# EEZ_DIB_DCM220_r2B5.net
KiCad netlist of a schematic drawn in EAGLE
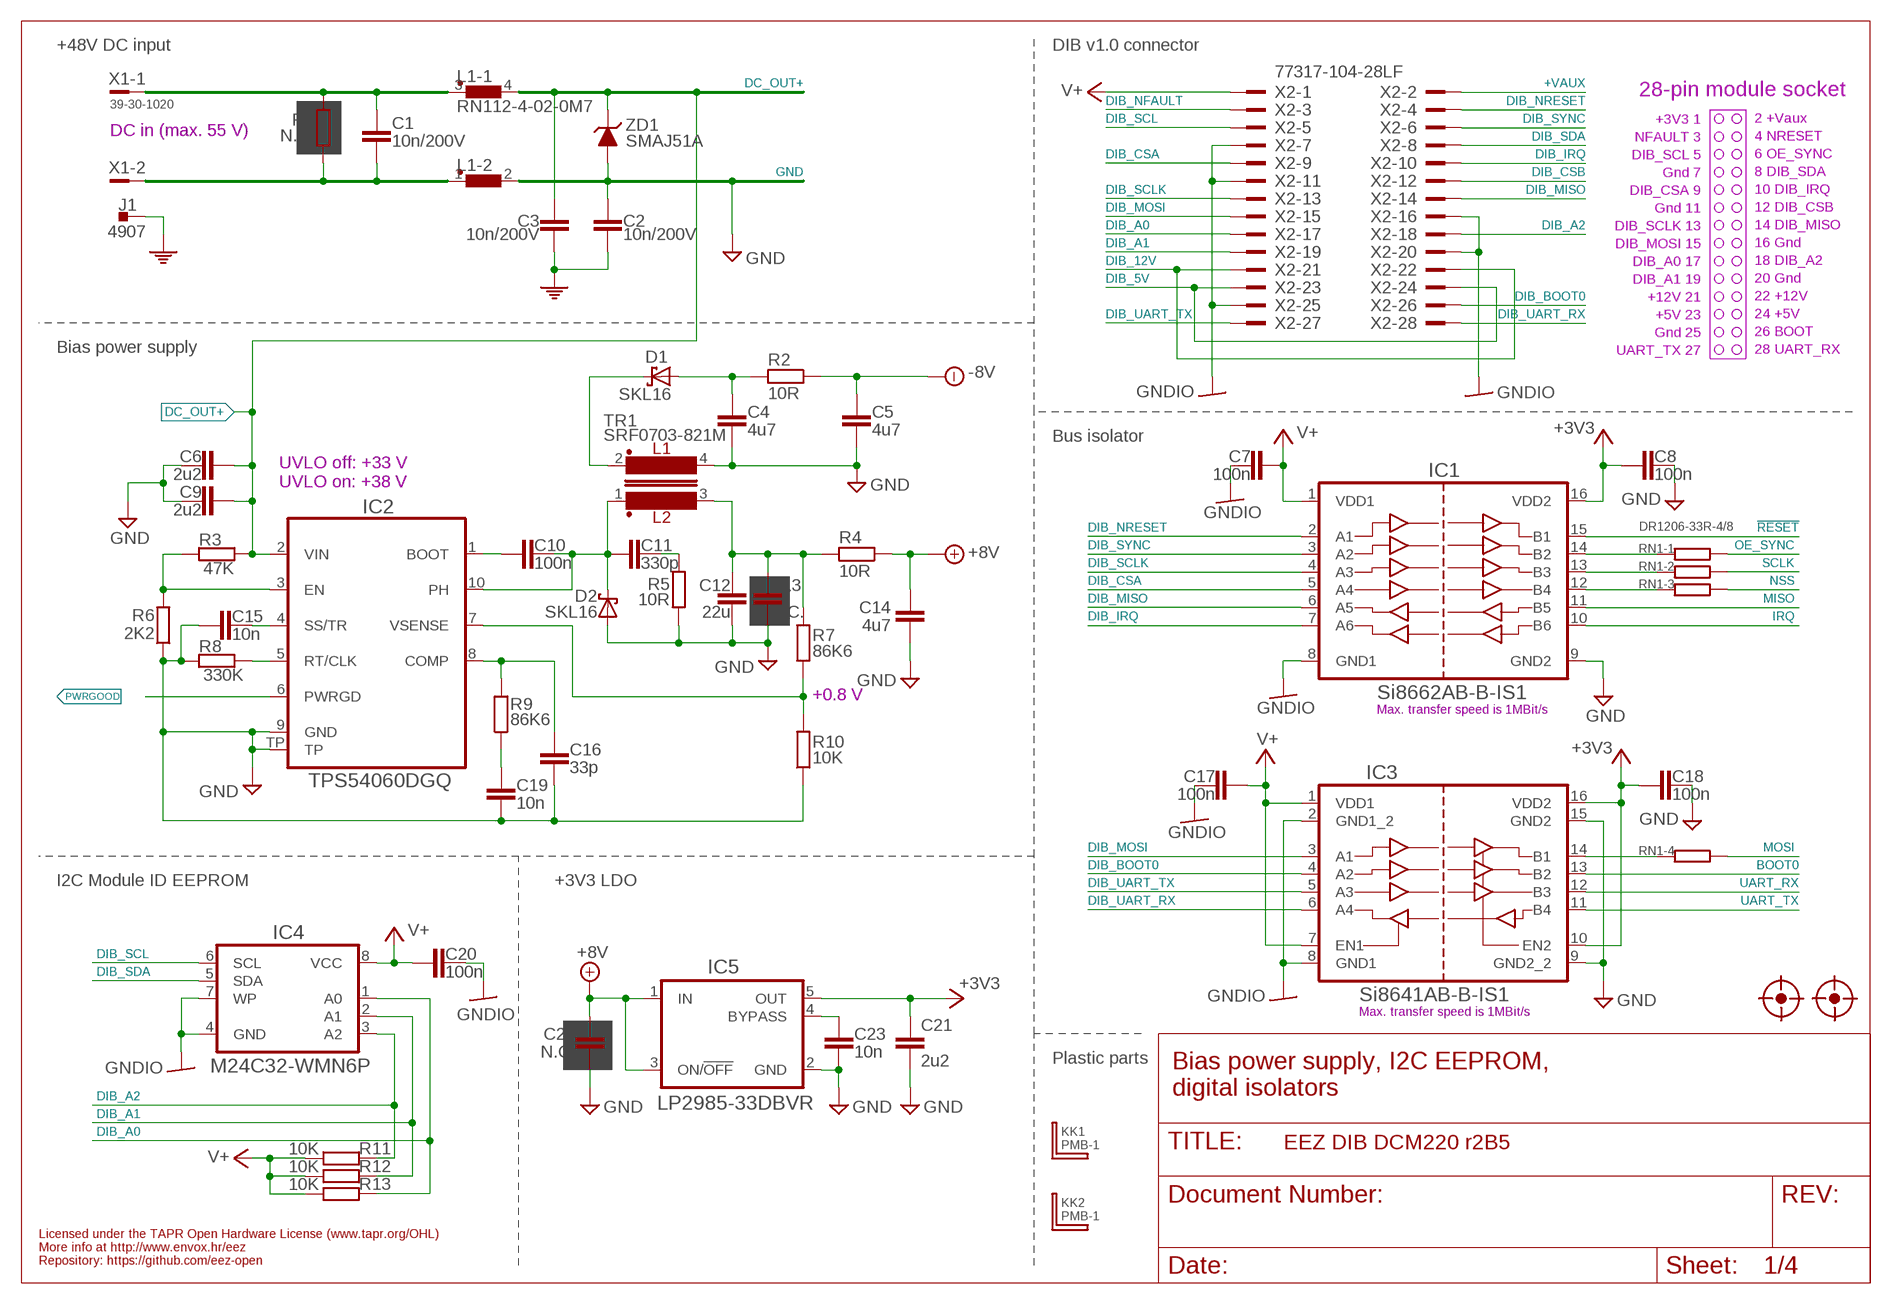
[diagram p0: schematic, sheet 1]
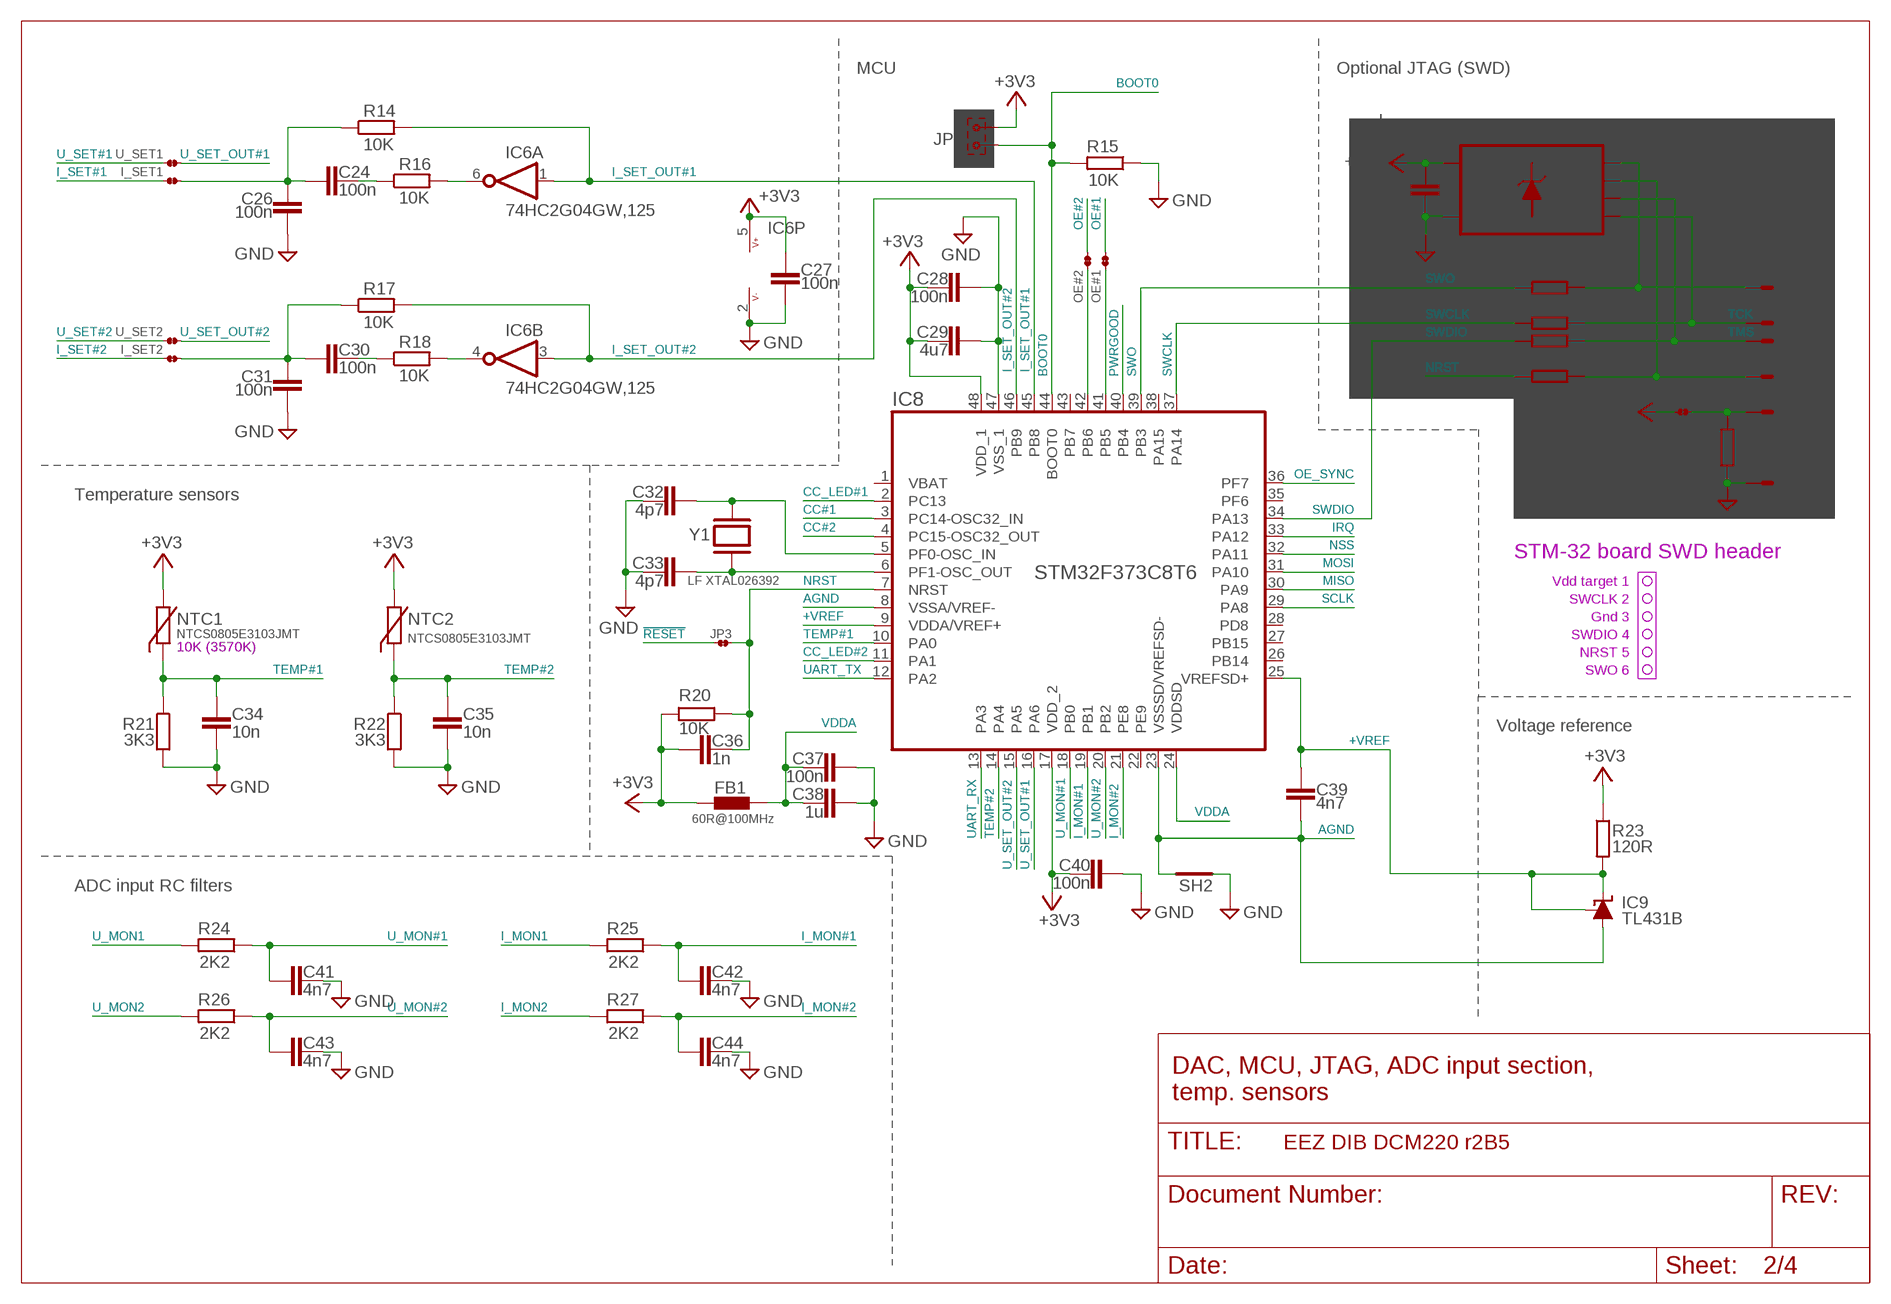
[diagram p1: schematic, sheet 2]
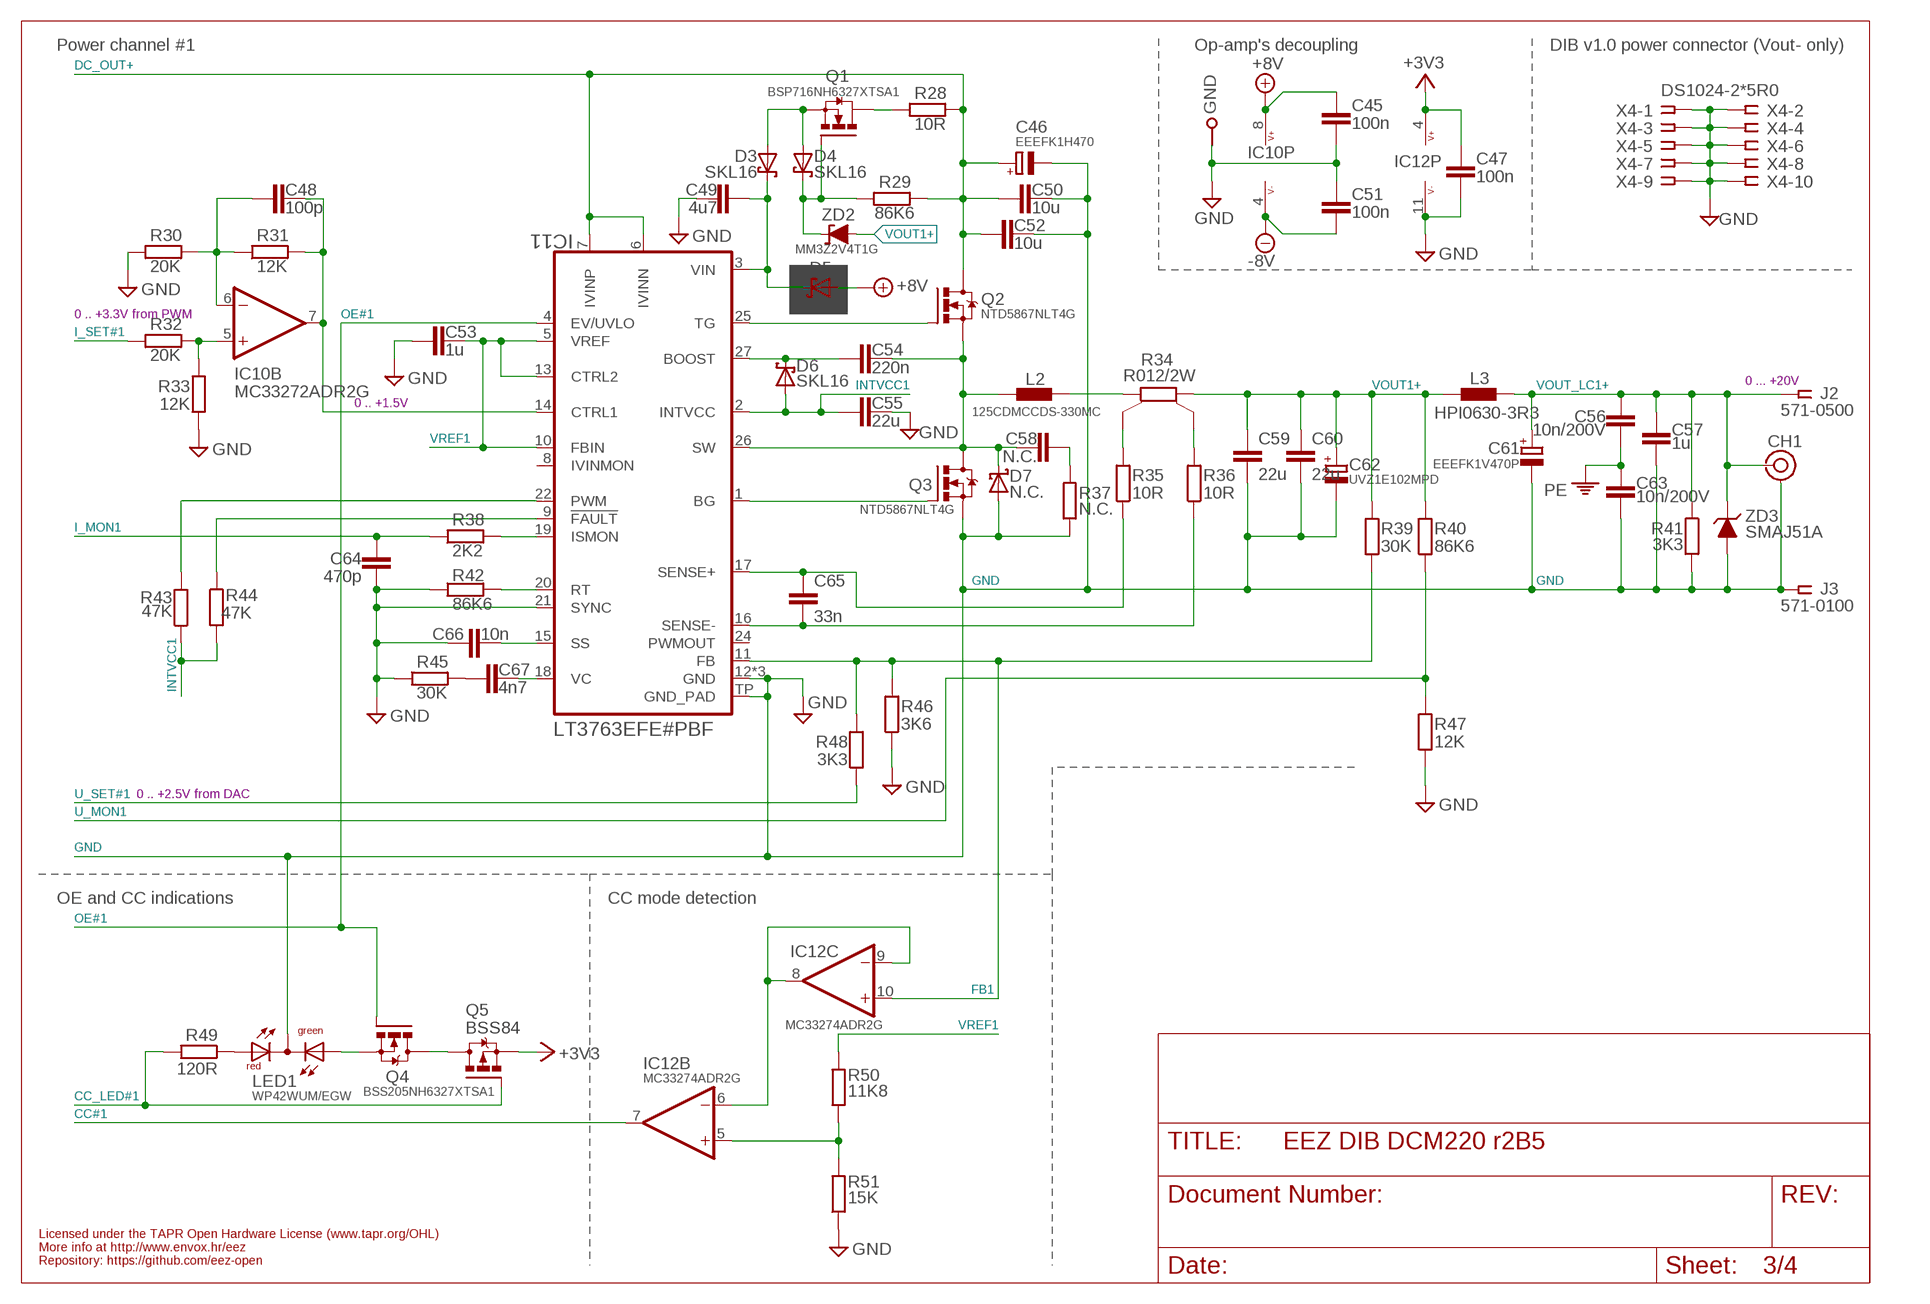
[diagram p2: schematic, sheet 3]
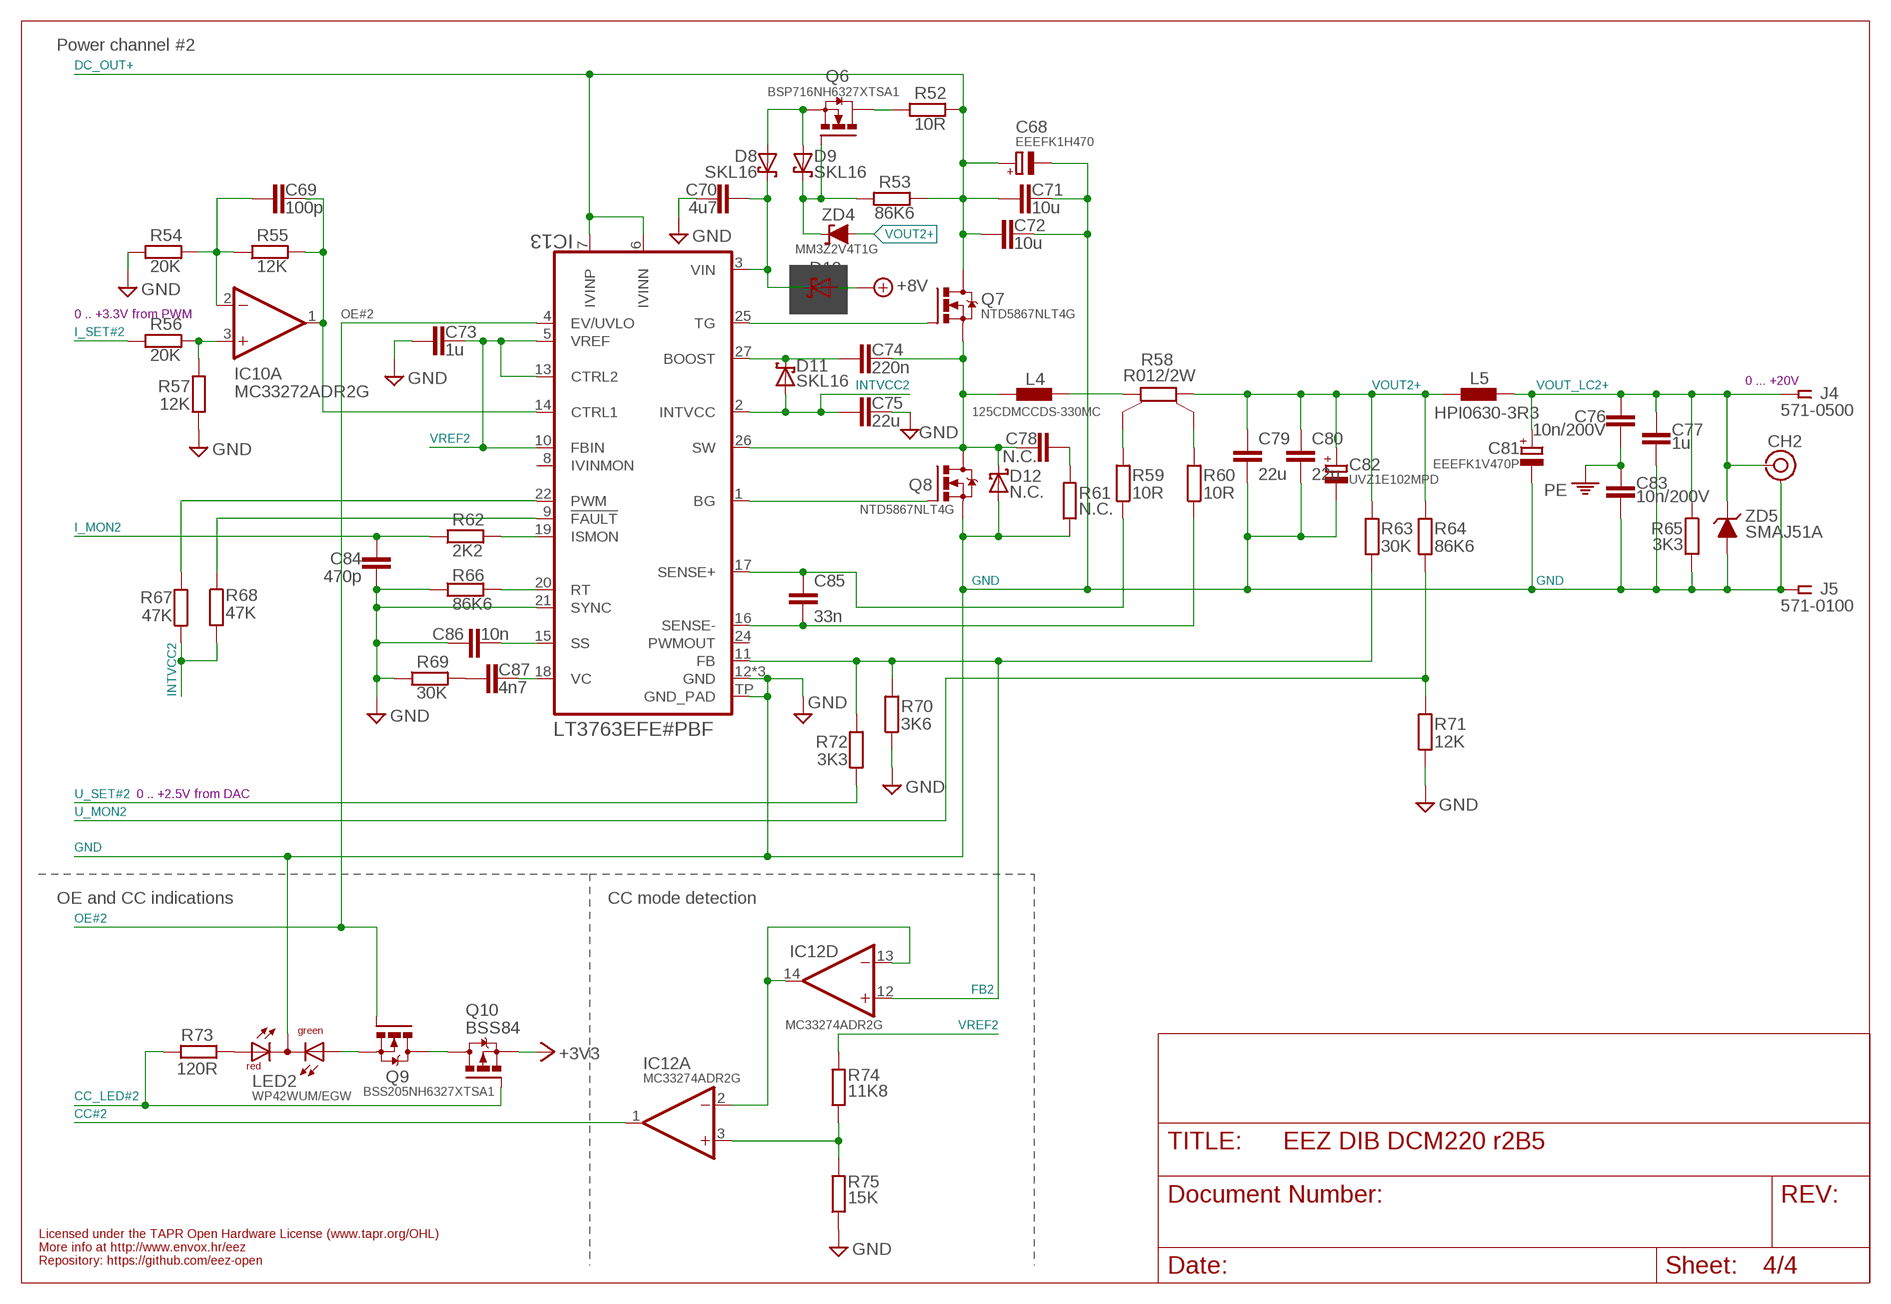
[diagram p3: schematic, sheet 4]

(export (version "E")
  (design (tool "Eeschema 10.0.6"))
  (components
    (comp (ref "C24")
      (value "100n")
      (footprint "eagle-import:C0603")
      (libsource (lib "eagle-import") (part "C-EUC0603"))
    )
    (comp (ref "C25")
      (value "N.C.")
      (footprint "eagle-import:C0603")
      (libsource (lib "eagle-import") (part "C-EUC0603"))
    )
    (comp (ref "C26")
      (value "100n")
      (footprint "eagle-import:C0603")
      (libsource (lib "eagle-import") (part "C-EUC0603"))
    )
    (comp (ref "C27")
      (value "100n")
      (footprint "eagle-import:C0603")
      (libsource (lib "eagle-import") (part "C-EUC0603"))
    )
    (comp (ref "C28")
      (value "100n")
      (footprint "eagle-import:C0603")
      (libsource (lib "eagle-import") (part "C-EUC0603"))
    )
    (comp (ref "C29")
      (value "4u7")
      (footprint "eagle-import:C1206")
      (libsource (lib "eagle-import") (part "C-EUC1206"))
    )
    (comp (ref "C30")
      (value "100n")
      (footprint "eagle-import:C0603")
      (libsource (lib "eagle-import") (part "C-EUC0603"))
    )
    (comp (ref "C31")
      (value "100n")
      (footprint "eagle-import:C0603")
      (libsource (lib "eagle-import") (part "C-EUC0603"))
    )
    (comp (ref "C32")
      (value "4p7")
      (footprint "eagle-import:C0603")
      (libsource (lib "eagle-import") (part "C-EUC0603"))
    )
    (comp (ref "C33")
      (value "4p7")
      (footprint "eagle-import:C0603")
      (libsource (lib "eagle-import") (part "C-EUC0603"))
    )
    (comp (ref "C34")
      (value "10n")
      (footprint "eagle-import:C0805")
      (libsource (lib "eagle-import") (part "C-EUC0805"))
    )
    (comp (ref "C35")
      (value "10n")
      (footprint "eagle-import:C0805")
      (libsource (lib "eagle-import") (part "C-EUC0805"))
    )
    (comp (ref "C36")
      (value "1n")
      (footprint "eagle-import:C0805")
      (libsource (lib "eagle-import") (part "C-EUC0805"))
    )
    (comp (ref "C37")
      (value "100n")
      (footprint "eagle-import:C0603")
      (libsource (lib "eagle-import") (part "C-EUC0603"))
    )
    (comp (ref "C38")
      (value "1u")
      (footprint "eagle-import:C0805")
      (libsource (lib "eagle-import") (part "C-EUC0805"))
    )
    (comp (ref "C39")
      (value "4n7")
      (footprint "eagle-import:C0805")
      (libsource (lib "eagle-import") (part "C-EUC0805"))
    )
    (comp (ref "C40")
      (value "100n")
      (footprint "eagle-import:C0603")
      (libsource (lib "eagle-import") (part "C-EUC0603"))
    )
    (comp (ref "C41")
      (value "4n7")
      (footprint "eagle-import:C0805")
      (libsource (lib "eagle-import") (part "C-EUC0805"))
    )
    (comp (ref "C42")
      (value "4n7")
      (footprint "eagle-import:C0805")
      (libsource (lib "eagle-import") (part "C-EUC0805"))
    )
    (comp (ref "C43")
      (value "4n7")
      (footprint "eagle-import:C0805")
      (libsource (lib "eagle-import") (part "C-EUC0805"))
    )
    (comp (ref "C44")
      (value "4n7")
      (footprint "eagle-import:C0805")
      (libsource (lib "eagle-import") (part "C-EUC0805"))
    )
    (comp (ref "FB1")
      (value "60R@100MHz")
      (footprint "eagle-import:BEAD0603")
      (libsource (lib "eagle-import") (part "FERRITE_BEAD0603"))
    )
    (comp (ref "IC6")
      (value "74HC2G04GW,125")
      (footprint "eagle-import:SOT65P210X110-6N")
      (libsource (lib "eagle-import") (part "74HC2G04"))
    )
    (comp (ref "IC7")
      (value "N.C.")
      (footprint "eagle-import:DRL6")
      (libsource (lib "eagle-import") (part "TPD4E001-DRL"))
    )
    (comp (ref "IC8")
      (value "STM32F373C8T6")
      (footprint "eagle-import:LQFP-48")
      (libsource (lib "eagle-import") (part "STM32F373C8T6"))
    )
    (comp (ref "IC9")
      (value "TL431B")
      (footprint "eagle-import:SOT103P240X110-3N")
      (libsource (lib "eagle-import") (part "TL431"))
    )
    (comp (ref "I_SET1")
      (value "JP2-NOCUT")
      (footprint "eagle-import:JP2-NOCUT")
      (libsource (lib "eagle-import") (part "JP2-NOCUT"))
    )
    (comp (ref "I_SET2")
      (value "JP2-NOCUT")
      (footprint "eagle-import:JP2-NOCUT")
      (libsource (lib "eagle-import") (part "JP2-NOCUT"))
    )
    (comp (ref "JP1")
      (value "JUMPER-2PIN-2MM")
      (footprint "eagle-import:2MM-2")
      (libsource (lib "eagle-import") (part "JUMPER-2PIN-2MM"))
    )
    (comp (ref "JP2")
      (value "JP2-CUT")
      (footprint "eagle-import:JP2-CUT")
      (libsource (lib "eagle-import") (part "JP2-CUT"))
    )
    (comp (ref "JP3")
      (value "JP2-NOCUT")
      (footprint "eagle-import:JP2-NOCUT")
      (libsource (lib "eagle-import") (part "JP2-NOCUT"))
    )
    (comp (ref "NTC1")
      (value "NTCS0805E3103JMT")
      (footprint "eagle-import:R_0805")
      (libsource (lib "eagle-import") (part "NTCR_0805"))
    )
    (comp (ref "NTC2")
      (value "NTCS0805E3103JMT")
      (footprint "eagle-import:R_0805")
      (libsource (lib "eagle-import") (part "NTCR_0805"))
    )
    (comp (ref "OE#1")
      (value "JP2-NOCUT")
      (footprint "eagle-import:JP2-NOCUT")
      (libsource (lib "eagle-import") (part "JP2-NOCUT"))
    )
    (comp (ref "OE#2")
      (value "JP2-NOCUT")
      (footprint "eagle-import:JP2-NOCUT")
      (libsource (lib "eagle-import") (part "JP2-NOCUT"))
    )
    (comp (ref "R14")
      (value "10K")
      (footprint "eagle-import:R0805")
      (libsource (lib "eagle-import") (part "R-EU_R0805"))
    )
    (comp (ref "R15")
      (value "10K")
      (footprint "eagle-import:R0805")
      (libsource (lib "eagle-import") (part "R-EU_R0805"))
    )
    (comp (ref "R16")
      (value "10K")
      (footprint "eagle-import:R0805")
      (libsource (lib "eagle-import") (part "R-EU_R0805"))
    )
    (comp (ref "R17")
      (value "10K")
      (footprint "eagle-import:R0805")
      (libsource (lib "eagle-import") (part "R-EU_R0805"))
    )
    (comp (ref "R18")
      (value "10K")
      (footprint "eagle-import:R0805")
      (libsource (lib "eagle-import") (part "R-EU_R0805"))
    )
    (comp (ref "R19")
      (value "N.C.")
      (footprint "eagle-import:R0805")
      (libsource (lib "eagle-import") (part "R-EU_R0805"))
    )
    (comp (ref "R20")
      (value "10K")
      (footprint "eagle-import:R0805")
      (libsource (lib "eagle-import") (part "R-EU_R0805"))
    )
    (comp (ref "R21")
      (value "3K3")
      (footprint "eagle-import:R0805")
      (libsource (lib "eagle-import") (part "R-EU_R0805"))
    )
    (comp (ref "R22")
      (value "3K3")
      (footprint "eagle-import:R0805")
      (libsource (lib "eagle-import") (part "R-EU_R0805"))
    )
    (comp (ref "R23")
      (value "120R")
      (footprint "eagle-import:R0805")
      (libsource (lib "eagle-import") (part "R-EU_R0805"))
    )
    (comp (ref "R24")
      (value "2K2")
      (footprint "eagle-import:R0805")
      (libsource (lib "eagle-import") (part "R-EU_R0805"))
    )
    (comp (ref "R25")
      (value "2K2")
      (footprint "eagle-import:R0805")
      (libsource (lib "eagle-import") (part "R-EU_R0805"))
    )
    (comp (ref "R26")
      (value "2K2")
      (footprint "eagle-import:R0805")
      (libsource (lib "eagle-import") (part "R-EU_R0805"))
    )
    (comp (ref "R27")
      (value "2K2")
      (footprint "eagle-import:R0805")
      (libsource (lib "eagle-import") (part "R-EU_R0805"))
    )
    (comp (ref "RN2")
      (value "N.C.")
      (footprint "eagle-import:CAY16")
      (libsource (lib "eagle-import") (part "R_ARRAY4"))
    )
    (comp (ref "SH2")
      (value "SHORTNOHOLE")
      (footprint "eagle-import:SHORT_NOHOLE")
      (libsource (lib "eagle-import") (part "SHORTNOHOLE"))
    )
    (comp (ref "U_SET1")
      (value "JP2-NOCUT")
      (footprint "eagle-import:JP2-NOCUT")
      (libsource (lib "eagle-import") (part "JP2-NOCUT"))
    )
    (comp (ref "U_SET2")
      (value "JP2-NOCUT")
      (footprint "eagle-import:JP2-NOCUT")
      (libsource (lib "eagle-import") (part "JP2-NOCUT"))
    )
    (comp (ref "X3")
      (value "N.C.")
      (footprint "eagle-import:22-23-2061")
      (fields (field (name "MF") "MOLEX") (field (name "MPN") "22-23-2061"))
      (libsource (lib "eagle-import") (part "22-23-2061"))
    )
    (comp (ref "Y1")
      (value "LF XTAL026392")
      (footprint "eagle-import:12SMX(B)")
      (libsource (lib "eagle-import") (part "XTAL7.5X5.1-B"))
    )
    (comp (ref "C68")
      (value "EEEFK1H470")
      (footprint "eagle-import:CAPAE830X1050N")
      (libsource (lib "eagle-import") (part "ECAPSMD8.3MM/HA0"))
    )
    (comp (ref "C69")
      (value "100p")
      (footprint "eagle-import:C0805")
      (libsource (lib "eagle-import") (part "C-EUC0805"))
    )
    (comp (ref "C70")
      (value "4u7")
      (footprint "eagle-import:C1206")
      (libsource (lib "eagle-import") (part "C-EUC1206"))
    )
    (comp (ref "C71")
      (value "10u")
      (footprint "eagle-import:C1210")
      (libsource (lib "eagle-import") (part "C-EUC1210"))
    )
    (comp (ref "C72")
      (value "10u")
      (footprint "eagle-import:C1210")
      (libsource (lib "eagle-import") (part "C-EUC1210"))
    )
    (comp (ref "C73")
      (value "1u")
      (footprint "eagle-import:C0805")
      (libsource (lib "eagle-import") (part "C-EUC0805"))
    )
    (comp (ref "C74")
      (value "220n")
      (footprint "eagle-import:C0805")
      (libsource (lib "eagle-import") (part "C-EUC0805"))
    )
    (comp (ref "C75")
      (value "22u")
      (footprint "eagle-import:C1206")
      (libsource (lib "eagle-import") (part "C-EUC1206"))
    )
    (comp (ref "C76")
      (value "10n/200V")
      (footprint "eagle-import:C1206")
      (libsource (lib "eagle-import") (part "C-EUC1206"))
    )
    (comp (ref "C77")
      (value "1u")
      (footprint "eagle-import:C0805")
      (libsource (lib "eagle-import") (part "C-EUC0805"))
    )
    (comp (ref "C78")
      (value "N.C.")
      (footprint "eagle-import:C0805")
      (libsource (lib "eagle-import") (part "C-EUC0805"))
    )
    (comp (ref "C79")
      (value "22u")
      (footprint "eagle-import:C1210")
      (libsource (lib "eagle-import") (part "C-EUC1210"))
    )
    (comp (ref "C80")
      (value "22u")
      (footprint "eagle-import:C1210")
      (libsource (lib "eagle-import") (part "C-EUC1210"))
    )
    (comp (ref "C81")
      (value "EEEFK1V470P")
      (footprint "eagle-import:CAPAE660X610N")
      (libsource (lib "eagle-import") (part "ECAPPANASONIC_H"))
    )
    (comp (ref "C82")
      (value "UVZ1E102MPD")
      (footprint "eagle-import:ECAP5_10.5")
      (libsource (lib "eagle-import") (part "ECAP5G_10.5MM"))
    )
    (comp (ref "C83")
      (value "10n/200V")
      (footprint "eagle-import:C1206")
      (libsource (lib "eagle-import") (part "C-EUC1206"))
    )
    (comp (ref "C84")
      (value "470p")
      (footprint "eagle-import:C0805")
      (libsource (lib "eagle-import") (part "C-EUC0805"))
    )
    (comp (ref "C85")
      (value "33n")
      (footprint "eagle-import:C0805")
      (libsource (lib "eagle-import") (part "C-EUC0805"))
    )
    (comp (ref "C86")
      (value "10n")
      (footprint "eagle-import:C0805")
      (libsource (lib "eagle-import") (part "C-EUC0805"))
    )
    (comp (ref "C87")
      (value "4n7")
      (footprint "eagle-import:C0805")
      (libsource (lib "eagle-import") (part "C-EUC0805"))
    )
    (comp (ref "CH2")
      (value "TEST_POINT-2")
      (footprint "eagle-import:TP_1.1MM_2")
      (libsource (lib "eagle-import") (part "TEST_POINT-2"))
    )
    (comp (ref "D8")
      (value "SKL16")
      (footprint "eagle-import:SOD123")
      (libsource (lib "eagle-import") (part "SCHOTTKYSOD123"))
    )
    (comp (ref "D9")
      (value "SKL16")
      (footprint "eagle-import:SOD123")
      (libsource (lib "eagle-import") (part "SCHOTTKYSOD123"))
    )
    (comp (ref "D10")
      (value "N.C.")
      (footprint "eagle-import:SOD123")
      (libsource (lib "eagle-import") (part "SCHOTTKYSOD123"))
    )
    (comp (ref "D11")
      (value "SKL16")
      (footprint "eagle-import:SOD123")
      (libsource (lib "eagle-import") (part "SCHOTTKYSOD123"))
    )
    (comp (ref "D12")
      (value "N.C.")
      (footprint "eagle-import:SMA")
      (libsource (lib "eagle-import") (part "SCHOTTKYSMA_DO-214AC"))
    )
    (comp (ref "IC10")
      (value "MC33272ADR2G")
      (footprint "eagle-import:SOIC127P600X173-8N")
      (libsource (lib "eagle-import") (part "TL072SOIC8"))
    )
    (comp (ref "IC12")
      (value "MC33274ADR2G")
      (footprint "eagle-import:SOIC127P600X175-14N")
      (fields (field (name "MPN") "TL074ACD"))
      (libsource (lib "eagle-import") (part "TL074SOIC14"))
    )
    (comp (ref "IC13")
      (value "LT3763EFE#PBF")
      (footprint "eagle-import:LTC_05-08-1663-EB")
      (libsource (lib "eagle-import") (part "LT3763EFE#PBF"))
    )
    (comp (ref "J4")
      (value "571-0500")
      (footprint "eagle-import:DELTRON_571")
      (libsource (lib "eagle-import") (part "571-0500"))
    )
    (comp (ref "J5")
      (value "571-0100")
      (footprint "eagle-import:DELTRON_571")
      (libsource (lib "eagle-import") (part "571-0100"))
    )
    (comp (ref "L4")
      (value "125CDMCCDS-330MC")
      (footprint "eagle-import:125CDMCC_DS")
      (libsource (lib "eagle-import") (part "125CDMCC/DS"))
    )
    (comp (ref "L5")
      (value "HPI0630-3R3")
      (footprint "eagle-import:COILCRAFT_HPI0630")
      (libsource (lib "eagle-import") (part "COILCRAFT_HPI0630"))
    )
    (comp (ref "LED2")
      (value "WP42WUM/EGW")
      (footprint "eagle-import:L-42WUM-1EGWT")
      (libsource (lib "eagle-import") (part "LED_L-42WUM/1EGWT"))
    )
    (comp (ref "Q6")
      (value "BSP716NH6327XTSA1")
      (footprint "eagle-import:SOT223")
      (libsource (lib "eagle-import") (part "N-HEXFET-2D_?-SOT232IRLL014N"))
    )
    (comp (ref "Q7")
      (value "NTD5867NLT4G")
      (footprint "eagle-import:TO229P990X239-3N")
      (libsource (lib "eagle-import") (part "N-MOSFETDPAK"))
    )
    (comp (ref "Q8")
      (value "NTD5867NLT4G")
      (footprint "eagle-import:TO229P990X239-3N")
      (libsource (lib "eagle-import") (part "N-MOSFETDPAK"))
    )
    (comp (ref "Q9")
      (value "BSS205NH6327XTSA1")
      (footprint "eagle-import:SOT103P240X110-3N")
      (fields (field (name "MPN") "2N7002-7-F"))
      (libsource (lib "eagle-import") (part "2N7002"))
    )
    (comp (ref "Q10")
      (value "BSS84")
      (footprint "eagle-import:SOT95P237X112-3N")
      (fields (field (name "MPN") "IRLML2246TRPBF"))
      (libsource (lib "eagle-import") (part "IRLML2246TRPBF"))
    )
    (comp (ref "R52")
      (value "10R")
      (footprint "eagle-import:R0805")
      (libsource (lib "eagle-import") (part "R-EU_R0805"))
    )
    (comp (ref "R53")
      (value "86K6")
      (footprint "eagle-import:R0805")
      (libsource (lib "eagle-import") (part "R-EU_R0805"))
    )
    (comp (ref "R54")
      (value "20K")
      (footprint "eagle-import:R0805")
      (libsource (lib "eagle-import") (part "R-EU_R0805"))
    )
    (comp (ref "R55")
      (value "12K")
      (footprint "eagle-import:R0805")
      (libsource (lib "eagle-import") (part "R-EU_R0805"))
    )
    (comp (ref "R56")
      (value "20K")
      (footprint "eagle-import:R0805")
      (libsource (lib "eagle-import") (part "R-EU_R0805"))
    )
    (comp (ref "R57")
      (value "12K")
      (footprint "eagle-import:R0805")
      (libsource (lib "eagle-import") (part "R-EU_R0805"))
    )
    (comp (ref "R58")
      (value "R012/2W")
      (footprint "eagle-import:R_2512-4WIRE")
      (libsource (lib "eagle-import") (part "R-EU_4WIRE2512"))
    )
    (comp (ref "R59")
      (value "10R")
      (footprint "eagle-import:R0805")
      (libsource (lib "eagle-import") (part "R-EU_R0805"))
    )
    (comp (ref "R60")
      (value "10R")
      (footprint "eagle-import:R0805")
      (libsource (lib "eagle-import") (part "R-EU_R0805"))
    )
    (comp (ref "R61")
      (value "N.C.")
      (footprint "eagle-import:R1206")
      (libsource (lib "eagle-import") (part "R-EU_R1206"))
    )
    (comp (ref "R62")
      (value "2K2")
      (footprint "eagle-import:R0805")
      (libsource (lib "eagle-import") (part "R-EU_R0805"))
    )
    (comp (ref "R63")
      (value "30K")
      (footprint "eagle-import:R0805")
      (libsource (lib "eagle-import") (part "R-EU_R0805"))
    )
    (comp (ref "R64")
      (value "86K6")
      (footprint "eagle-import:R0805")
      (libsource (lib "eagle-import") (part "R-EU_R0805"))
    )
    (comp (ref "R65")
      (value "3K3")
      (footprint "eagle-import:R0805")
      (libsource (lib "eagle-import") (part "R-EU_R0805"))
    )
    (comp (ref "R66")
      (value "86K6")
      (footprint "eagle-import:R0805")
      (libsource (lib "eagle-import") (part "R-EU_R0805"))
    )
    (comp (ref "R67")
      (value "47K")
      (footprint "eagle-import:R0805")
      (libsource (lib "eagle-import") (part "R-EU_R0805"))
    )
    (comp (ref "R68")
      (value "47K")
      (footprint "eagle-import:R0805")
      (libsource (lib "eagle-import") (part "R-EU_R0805"))
    )
    (comp (ref "R69")
      (value "30K")
      (footprint "eagle-import:R0805")
      (libsource (lib "eagle-import") (part "R-EU_R0805"))
    )
    (comp (ref "R70")
      (value "3K6")
      (footprint "eagle-import:R0805")
      (libsource (lib "eagle-import") (part "R-EU_R0805"))
    )
    (comp (ref "R71")
      (value "12K")
      (footprint "eagle-import:R0805")
      (libsource (lib "eagle-import") (part "R-EU_R0805"))
    )
    (comp (ref "R72")
      (value "3K3")
      (footprint "eagle-import:R0805")
      (libsource (lib "eagle-import") (part "R-EU_R0805"))
    )
    (comp (ref "R73")
      (value "120R")
      (footprint "eagle-import:R0805")
      (libsource (lib "eagle-import") (part "R-EU_R0805"))
    )
    (comp (ref "R74")
      (value "11K8")
      (footprint "eagle-import:R0805")
      (libsource (lib "eagle-import") (part "R-EU_R0805"))
    )
    (comp (ref "R75")
      (value "15K")
      (footprint "eagle-import:R0805")
      (libsource (lib "eagle-import") (part "R-EU_R0805"))
    )
    (comp (ref "ZD4")
      (value "MM3Z2V4T1G")
      (footprint "eagle-import:SOD323-W")
      (libsource (lib "eagle-import") (part "ZENER-DIODESOD323"))
    )
    (comp (ref "ZD5")
      (value "SMAJ51A")
      (footprint "eagle-import:DO214AA")
      (libsource (lib "eagle-import") (part "P6SMB68A"))
    )
    (comp (ref "C45")
      (value "100n")
      (footprint "eagle-import:C0603")
      (libsource (lib "eagle-import") (part "C-EUC0603"))
    )
    (comp (ref "C46")
      (value "EEEFK1H470")
      (footprint "eagle-import:CAPAE830X1050N")
      (libsource (lib "eagle-import") (part "ECAPSMD8.3MM/HA0"))
    )
    (comp (ref "C47")
      (value "100n")
      (footprint "eagle-import:C0603")
      (libsource (lib "eagle-import") (part "C-EUC0603"))
    )
    (comp (ref "C48")
      (value "100p")
      (footprint "eagle-import:C0805")
      (libsource (lib "eagle-import") (part "C-EUC0805"))
    )
    (comp (ref "C49")
      (value "4u7")
      (footprint "eagle-import:C1206")
      (libsource (lib "eagle-import") (part "C-EUC1206"))
    )
    (comp (ref "C50")
      (value "10u")
      (footprint "eagle-import:C1210")
      (libsource (lib "eagle-import") (part "C-EUC1210"))
    )
    (comp (ref "C51")
      (value "100n")
      (footprint "eagle-import:C0603")
      (libsource (lib "eagle-import") (part "C-EUC0603"))
    )
    (comp (ref "C52")
      (value "10u")
      (footprint "eagle-import:C1210")
      (libsource (lib "eagle-import") (part "C-EUC1210"))
    )
    (comp (ref "C53")
      (value "1u")
      (footprint "eagle-import:C0805")
      (libsource (lib "eagle-import") (part "C-EUC0805"))
    )
    (comp (ref "C54")
      (value "220n")
      (footprint "eagle-import:C0805")
      (libsource (lib "eagle-import") (part "C-EUC0805"))
    )
    (comp (ref "C55")
      (value "22u")
      (footprint "eagle-import:C1206")
      (libsource (lib "eagle-import") (part "C-EUC1206"))
    )
    (comp (ref "C56")
      (value "10n/200V")
      (footprint "eagle-import:C1206")
      (libsource (lib "eagle-import") (part "C-EUC1206"))
    )
    (comp (ref "C57")
      (value "1u")
      (footprint "eagle-import:C0805")
      (libsource (lib "eagle-import") (part "C-EUC0805"))
    )
    (comp (ref "C58")
      (value "N.C.")
      (footprint "eagle-import:C0805")
      (libsource (lib "eagle-import") (part "C-EUC0805"))
    )
    (comp (ref "C59")
      (value "22u")
      (footprint "eagle-import:C1210")
      (libsource (lib "eagle-import") (part "C-EUC1210"))
    )
    (comp (ref "C60")
      (value "22u")
      (footprint "eagle-import:C1210")
      (libsource (lib "eagle-import") (part "C-EUC1210"))
    )
    (comp (ref "C61")
      (value "EEEFK1V470P")
      (footprint "eagle-import:CAPAE660X610N")
      (libsource (lib "eagle-import") (part "ECAPPANASONIC_H"))
    )
    (comp (ref "C62")
      (value "UVZ1E102MPD")
      (footprint "eagle-import:ECAP5_10.5")
      (libsource (lib "eagle-import") (part "ECAP5G_10.5MM"))
    )
    (comp (ref "C63")
      (value "10n/200V")
      (footprint "eagle-import:C1206")
      (libsource (lib "eagle-import") (part "C-EUC1206"))
    )
    (comp (ref "C64")
      (value "470p")
      (footprint "eagle-import:C0805")
      (libsource (lib "eagle-import") (part "C-EUC0805"))
    )
    (comp (ref "C65")
      (value "33n")
      (footprint "eagle-import:C0805")
      (libsource (lib "eagle-import") (part "C-EUC0805"))
    )
    (comp (ref "C66")
      (value "10n")
      (footprint "eagle-import:C0805")
      (libsource (lib "eagle-import") (part "C-EUC0805"))
    )
    (comp (ref "C67")
      (value "4n7")
      (footprint "eagle-import:C0805")
      (libsource (lib "eagle-import") (part "C-EUC0805"))
    )
    (comp (ref "CH1")
      (value "TEST_POINT-2")
      (footprint "eagle-import:TP_1.1MM_2")
      (libsource (lib "eagle-import") (part "TEST_POINT-2"))
    )
    (comp (ref "D3")
      (value "SKL16")
      (footprint "eagle-import:SOD123")
      (libsource (lib "eagle-import") (part "SCHOTTKYSOD123"))
    )
    (comp (ref "D4")
      (value "SKL16")
      (footprint "eagle-import:SOD123")
      (libsource (lib "eagle-import") (part "SCHOTTKYSOD123"))
    )
    (comp (ref "D5")
      (value "N.C.")
      (footprint "eagle-import:SOD123")
      (libsource (lib "eagle-import") (part "SCHOTTKYSOD123"))
    )
    (comp (ref "D6")
      (value "SKL16")
      (footprint "eagle-import:SOD123")
      (libsource (lib "eagle-import") (part "SCHOTTKYSOD123"))
    )
    (comp (ref "D7")
      (value "N.C.")
      (footprint "eagle-import:SMA")
      (libsource (lib "eagle-import") (part "SCHOTTKYSMA_DO-214AC"))
    )
    (comp (ref "GND")
      (value "TEST-PIN_0.9MM")
      (footprint "eagle-import:TEST-PIN_0.9MM")
      (libsource (lib "eagle-import") (part "TEST-PIN_0.9MM"))
    )
    (comp (ref "IC11")
      (value "LT3763EFE#PBF")
      (footprint "eagle-import:LTC_05-08-1663-EB")
      (libsource (lib "eagle-import") (part "LT3763EFE#PBF"))
    )
    (comp (ref "J2")
      (value "571-0500")
      (footprint "eagle-import:DELTRON_571")
      (libsource (lib "eagle-import") (part "571-0500"))
    )
    (comp (ref "J3")
      (value "571-0100")
      (footprint "eagle-import:DELTRON_571")
      (libsource (lib "eagle-import") (part "571-0100"))
    )
    (comp (ref "L2")
      (value "125CDMCCDS-330MC")
      (footprint "eagle-import:125CDMCC_DS")
      (libsource (lib "eagle-import") (part "125CDMCC/DS"))
    )
    (comp (ref "L3")
      (value "HPI0630-3R3")
      (footprint "eagle-import:COILCRAFT_HPI0630")
      (libsource (lib "eagle-import") (part "COILCRAFT_HPI0630"))
    )
    (comp (ref "LED1")
      (value "WP42WUM/EGW")
      (footprint "eagle-import:L-42WUM-1EGWT")
      (libsource (lib "eagle-import") (part "LED_L-42WUM/1EGWT"))
    )
    (comp (ref "Q1")
      (value "BSP716NH6327XTSA1")
      (footprint "eagle-import:SOT223")
      (libsource (lib "eagle-import") (part "N-HEXFET-2D_?-SOT232IRLL014N"))
    )
    (comp (ref "Q2")
      (value "NTD5867NLT4G")
      (footprint "eagle-import:TO229P990X239-3N")
      (libsource (lib "eagle-import") (part "N-MOSFETDPAK"))
    )
    (comp (ref "Q3")
      (value "NTD5867NLT4G")
      (footprint "eagle-import:TO229P990X239-3N")
      (libsource (lib "eagle-import") (part "N-MOSFETDPAK"))
    )
    (comp (ref "Q4")
      (value "BSS205NH6327XTSA1")
      (footprint "eagle-import:SOT103P240X110-3N")
      (fields (field (name "MPN") "2N7002-7-F"))
      (libsource (lib "eagle-import") (part "2N7002"))
    )
    (comp (ref "Q5")
      (value "BSS84")
      (footprint "eagle-import:SOT95P237X112-3N")
      (fields (field (name "MPN") "IRLML2246TRPBF"))
      (libsource (lib "eagle-import") (part "IRLML2246TRPBF"))
    )
    (comp (ref "R28")
      (value "10R")
      (footprint "eagle-import:R0805")
      (libsource (lib "eagle-import") (part "R-EU_R0805"))
    )
    (comp (ref "R29")
      (value "86K6")
      (footprint "eagle-import:R0805")
      (libsource (lib "eagle-import") (part "R-EU_R0805"))
    )
    (comp (ref "R30")
      (value "20K")
      (footprint "eagle-import:R0805")
      (libsource (lib "eagle-import") (part "R-EU_R0805"))
    )
    (comp (ref "R31")
      (value "12K")
      (footprint "eagle-import:R0805")
      (libsource (lib "eagle-import") (part "R-EU_R0805"))
    )
    (comp (ref "R32")
      (value "20K")
      (footprint "eagle-import:R0805")
      (libsource (lib "eagle-import") (part "R-EU_R0805"))
    )
    (comp (ref "R33")
      (value "12K")
      (footprint "eagle-import:R0805")
      (libsource (lib "eagle-import") (part "R-EU_R0805"))
    )
    (comp (ref "R34")
      (value "R012/2W")
      (footprint "eagle-import:R_2512-4WIRE")
      (libsource (lib "eagle-import") (part "R-EU_4WIRE2512"))
    )
    (comp (ref "R35")
      (value "10R")
      (footprint "eagle-import:R0805")
      (libsource (lib "eagle-import") (part "R-EU_R0805"))
    )
    (comp (ref "R36")
      (value "10R")
      (footprint "eagle-import:R0805")
      (libsource (lib "eagle-import") (part "R-EU_R0805"))
    )
    (comp (ref "R37")
      (value "N.C.")
      (footprint "eagle-import:R1206")
      (libsource (lib "eagle-import") (part "R-EU_R1206"))
    )
    (comp (ref "R38")
      (value "2K2")
      (footprint "eagle-import:R0805")
      (libsource (lib "eagle-import") (part "R-EU_R0805"))
    )
    (comp (ref "R39")
      (value "30K")
      (footprint "eagle-import:R0805")
      (libsource (lib "eagle-import") (part "R-EU_R0805"))
    )
    (comp (ref "R40")
      (value "86K6")
      (footprint "eagle-import:R0805")
      (libsource (lib "eagle-import") (part "R-EU_R0805"))
    )
    (comp (ref "R41")
      (value "3K3")
      (footprint "eagle-import:R0805")
      (libsource (lib "eagle-import") (part "R-EU_R0805"))
    )
    (comp (ref "R42")
      (value "86K6")
      (footprint "eagle-import:R0805")
      (libsource (lib "eagle-import") (part "R-EU_R0805"))
    )
    (comp (ref "R43")
      (value "47K")
      (footprint "eagle-import:R0805")
      (libsource (lib "eagle-import") (part "R-EU_R0805"))
    )
    (comp (ref "R44")
      (value "47K")
      (footprint "eagle-import:R0805")
      (libsource (lib "eagle-import") (part "R-EU_R0805"))
    )
    (comp (ref "R45")
      (value "30K")
      (footprint "eagle-import:R0805")
      (libsource (lib "eagle-import") (part "R-EU_R0805"))
    )
    (comp (ref "R46")
      (value "3K6")
      (footprint "eagle-import:R0805")
      (libsource (lib "eagle-import") (part "R-EU_R0805"))
    )
    (comp (ref "R47")
      (value "12K")
      (footprint "eagle-import:R0805")
      (libsource (lib "eagle-import") (part "R-EU_R0805"))
    )
    (comp (ref "R48")
      (value "3K3")
      (footprint "eagle-import:R0805")
      (libsource (lib "eagle-import") (part "R-EU_R0805"))
    )
    (comp (ref "R49")
      (value "120R")
      (footprint "eagle-import:R0805")
      (libsource (lib "eagle-import") (part "R-EU_R0805"))
    )
    (comp (ref "R50")
      (value "11K8")
      (footprint "eagle-import:R0805")
      (libsource (lib "eagle-import") (part "R-EU_R0805"))
    )
    (comp (ref "R51")
      (value "15K")
      (footprint "eagle-import:R0805")
      (libsource (lib "eagle-import") (part "R-EU_R0805"))
    )
    (comp (ref "X4")
      (value "DS1024-2*5R0")
      (footprint "eagle-import:SSW-105-02-T-D-RA")
      (libsource (lib "eagle-import") (part "SSW-105-02-T-D-RA"))
    )
    (comp (ref "ZD2")
      (value "MM3Z2V4T1G")
      (footprint "eagle-import:SOD323-W")
      (libsource (lib "eagle-import") (part "ZENER-DIODESOD323"))
    )
    (comp (ref "ZD3")
      (value "SMAJ51A")
      (footprint "eagle-import:DO214AA")
      (libsource (lib "eagle-import") (part "P6SMB68A"))
    )
    (comp (ref "C1")
      (value "10n/200V")
      (footprint "eagle-import:C1206")
      (libsource (lib "eagle-import") (part "C-EUC1206"))
    )
    (comp (ref "C2")
      (value "10n/200V")
      (footprint "eagle-import:C1206")
      (libsource (lib "eagle-import") (part "C-EUC1206"))
    )
    (comp (ref "C3")
      (value "10n/200V")
      (footprint "eagle-import:C1206")
      (libsource (lib "eagle-import") (part "C-EUC1206"))
    )
    (comp (ref "C4")
      (value "4u7")
      (footprint "eagle-import:C1206")
      (libsource (lib "eagle-import") (part "C-EUC1206"))
    )
    (comp (ref "C5")
      (value "4u7")
      (footprint "eagle-import:C1206")
      (libsource (lib "eagle-import") (part "C-EUC1206"))
    )
    (comp (ref "C6")
      (value "2u2")
      (footprint "eagle-import:C1206")
      (libsource (lib "eagle-import") (part "C-EUC1206"))
    )
    (comp (ref "C7")
      (value "100n")
      (footprint "eagle-import:C0603")
      (libsource (lib "eagle-import") (part "C-EUC0603"))
    )
    (comp (ref "C8")
      (value "100n")
      (footprint "eagle-import:C0603")
      (libsource (lib "eagle-import") (part "C-EUC0603"))
    )
    (comp (ref "C9")
      (value "2u2")
      (footprint "eagle-import:C1206")
      (libsource (lib "eagle-import") (part "C-EUC1206"))
    )
    (comp (ref "C10")
      (value "100n")
      (footprint "eagle-import:C0603")
      (libsource (lib "eagle-import") (part "C-EUC0603"))
    )
    (comp (ref "C11")
      (value "330p")
      (footprint "eagle-import:C0805")
      (libsource (lib "eagle-import") (part "C-EUC0805"))
    )
    (comp (ref "C12")
      (value "22u")
      (footprint "eagle-import:C1206")
      (libsource (lib "eagle-import") (part "C-EUC1206"))
    )
    (comp (ref "C13")
      (value "N.C.")
      (footprint "eagle-import:C1206")
      (libsource (lib "eagle-import") (part "C-EUC1206"))
    )
    (comp (ref "C14")
      (value "4u7")
      (footprint "eagle-import:C1206")
      (libsource (lib "eagle-import") (part "C-EUC1206"))
    )
    (comp (ref "C15")
      (value "10n")
      (footprint "eagle-import:C0805")
      (libsource (lib "eagle-import") (part "C-EUC0805"))
    )
    (comp (ref "C16")
      (value "33p")
      (footprint "eagle-import:C0603")
      (libsource (lib "eagle-import") (part "C-EUC0603"))
    )
    (comp (ref "C17")
      (value "100n")
      (footprint "eagle-import:C0603")
      (libsource (lib "eagle-import") (part "C-EUC0603"))
    )
    (comp (ref "C18")
      (value "100n")
      (footprint "eagle-import:C0603")
      (libsource (lib "eagle-import") (part "C-EUC0603"))
    )
    (comp (ref "C19")
      (value "10n")
      (footprint "eagle-import:C0805")
      (libsource (lib "eagle-import") (part "C-EUC0805"))
    )
    (comp (ref "C20")
      (value "100n")
      (footprint "eagle-import:C0603")
      (libsource (lib "eagle-import") (part "C-EUC0603"))
    )
    (comp (ref "C21")
      (value "2u2")
      (footprint "eagle-import:C1206")
      (libsource (lib "eagle-import") (part "C-EUC1206"))
    )
    (comp (ref "C22")
      (value "N.C.")
      (footprint "eagle-import:C0805")
      (libsource (lib "eagle-import") (part "C-EUC0805"))
    )
    (comp (ref "C23")
      (value "10n")
      (footprint "eagle-import:C0805")
      (libsource (lib "eagle-import") (part "C-EUC0805"))
    )
    (comp (ref "D1")
      (value "SKL16")
      (footprint "eagle-import:SOD123")
      (libsource (lib "eagle-import") (part "SCHOTTKYSOD123"))
    )
    (comp (ref "D2")
      (value "SKL16")
      (footprint "eagle-import:SOD123")
      (libsource (lib "eagle-import") (part "SCHOTTKYSOD123"))
    )
    (comp (ref "FM1")
      (value "FIDUCIAL_2")
      (footprint "eagle-import:FIDUCIAL_DUAL")
      (libsource (lib "eagle-import") (part "FIDUCIAL_2"))
    )
    (comp (ref "FM2")
      (value "FIDUCIAL_2")
      (footprint "eagle-import:FIDUCIAL_DUAL")
      (libsource (lib "eagle-import") (part "FIDUCIAL_2"))
    )
    (comp (ref "IC1")
      (value "Si8662AB-B-IS1")
      (footprint "eagle-import:SOIC-16")
      (libsource (lib "eagle-import") (part "SI8662NSOIC-16"))
    )
    (comp (ref "IC2")
      (value "TPS54060DGQ")
      (footprint "eagle-import:SOP50P490X110-11N")
      (fields (field (name "MPN") "TPS54060ADGQ"))
      (libsource (lib "eagle-import") (part "TPS54060DGQ"))
    )
    (comp (ref "IC3")
      (value "Si8641AB-B-IS1")
      (footprint "eagle-import:SOIC-16")
      (libsource (lib "eagle-import") (part "SI8641NSOIC-16"))
    )
    (comp (ref "IC4")
      (value "M24C32-WMN6P")
      (footprint "eagle-import:SOIC127P600X173-8N")
      (libsource (lib "eagle-import") (part "AT24CXXSOIC8"))
    )
    (comp (ref "IC5")
      (value "LP2985-33DBVR")
      (footprint "eagle-import:SOT95P270X145-5N")
      (libsource (lib "eagle-import") (part "LP2985"))
    )
    (comp (ref "J1")
      (value "4907")
      (footprint "eagle-import:PCB_TAB-4907")
      (libsource (lib "eagle-import") (part "PCB_TAB-4907"))
    )
    (comp (ref "KK1")
      (value "PMB-1")
      (footprint "eagle-import:PCB-MB")
      (libsource (lib "eagle-import") (part "PCB-MB"))
    )
    (comp (ref "KK2")
      (value "PMB-1")
      (footprint "eagle-import:PCB-MB")
      (libsource (lib "eagle-import") (part "PCB-MB"))
    )
    (comp (ref "L1")
      (value "RN112-4-02-0M7")
      (footprint "eagle-import:RN112")
      (libsource (lib "eagle-import") (part "RN112"))
    )
    (comp (ref "R1")
      (value "N.C.")
      (footprint "eagle-import:R2512")
      (libsource (lib "eagle-import") (part "R-EU_R2512"))
    )
    (comp (ref "R2")
      (value "10R")
      (footprint "eagle-import:R0805")
      (libsource (lib "eagle-import") (part "R-EU_R0805"))
    )
    (comp (ref "R3")
      (value "47K")
      (footprint "eagle-import:R0805")
      (libsource (lib "eagle-import") (part "R-EU_R0805"))
    )
    (comp (ref "R4")
      (value "10R")
      (footprint "eagle-import:R0805")
      (libsource (lib "eagle-import") (part "R-EU_R0805"))
    )
    (comp (ref "R5")
      (value "10R")
      (footprint "eagle-import:R0805")
      (libsource (lib "eagle-import") (part "R-EU_R0805"))
    )
    (comp (ref "R6")
      (value "2K2")
      (footprint "eagle-import:R0805")
      (libsource (lib "eagle-import") (part "R-EU_R0805"))
    )
    (comp (ref "R7")
      (value "86K6")
      (footprint "eagle-import:R0805")
      (libsource (lib "eagle-import") (part "R-EU_R0805"))
    )
    (comp (ref "R8")
      (value "330K")
      (footprint "eagle-import:R0805")
      (libsource (lib "eagle-import") (part "R-EU_R0805"))
    )
    (comp (ref "R9")
      (value "86K6")
      (footprint "eagle-import:R0805")
      (libsource (lib "eagle-import") (part "R-EU_R0805"))
    )
    (comp (ref "R10")
      (value "10K")
      (footprint "eagle-import:R0805")
      (libsource (lib "eagle-import") (part "R-EU_R0805"))
    )
    (comp (ref "R11")
      (value "10K")
      (footprint "eagle-import:R0805")
      (libsource (lib "eagle-import") (part "R-EU_R0805"))
    )
    (comp (ref "R12")
      (value "10K")
      (footprint "eagle-import:R0805")
      (libsource (lib "eagle-import") (part "R-EU_R0805"))
    )
    (comp (ref "R13")
      (value "10K")
      (footprint "eagle-import:R0805")
      (libsource (lib "eagle-import") (part "R-EU_R0805"))
    )
    (comp (ref "RN1")
      (value "DR1206-33R-4/8")
      (footprint "eagle-import:CAY16")
      (libsource (lib "eagle-import") (part "R_ARRAY4"))
    )
    (comp (ref "TR1")
      (value "SRF0703-821M")
      (footprint "eagle-import:SRF0703")
      (libsource (lib "eagle-import") (part "BOURNS_SRF0703INV"))
    )
    (comp (ref "X1")
      (value "39-30-1020")
      (footprint "eagle-import:MINIFIT_39301020")
      (libsource (lib "eagle-import") (part "MINIFIT_39301020"))
    )
    (comp (ref "X2")
      (value "77317-104-28LF")
      (footprint "eagle-import:77317-104-28LF")
      (libsource (lib "eagle-import") (part "77317-104-28LF"))
    )
    (comp (ref "ZD1")
      (value "SMAJ51A")
      (footprint "eagle-import:DO214AA")
      (libsource (lib "eagle-import") (part "P6SMB68A"))
    )
  )
  (nets
    (net (code "1") (name "+3V3") (class "Default")
      (node (ref "C18") (pin "2") (pinfunction "2_2") (pintype "passive"))
      (node (ref "C21") (pin "1") (pinfunction "1_1") (pintype "passive"))
      (node (ref "C25") (pin "1") (pinfunction "1_1") (pintype "passive"))
      (node (ref "C27") (pin "1") (pinfunction "1_1") (pintype "passive"))
      (node (ref "C28") (pin "2") (pinfunction "2_2") (pintype "passive"))
      (node (ref "C29") (pin "1") (pinfunction "1_1") (pintype "passive"))
      (node (ref "C36") (pin "2") (pinfunction "2_2") (pintype "passive"))
      (node (ref "C40") (pin "2") (pinfunction "2_2") (pintype "passive"))
      (node (ref "C47") (pin "1") (pinfunction "1_1") (pintype "passive"))
      (node (ref "C8") (pin "2") (pinfunction "2_2") (pintype "passive"))
      (node (ref "FB1") (pin "P$1") (pinfunction "1_P$1") (pintype "passive"))
      (node (ref "IC1") (pin "16") (pinfunction "VDD2_16") (pintype "passive"))
      (node (ref "IC12") (pin "4") (pinfunction "V+_4") (pintype "power_in"))
      (node (ref "IC3") (pin "10") (pinfunction "EN2_10") (pintype "input"))
      (node (ref "IC3") (pin "16") (pinfunction "VDD2_16") (pintype "passive"))
      (node (ref "IC5") (pin "5") (pinfunction "OUT_5") (pintype "passive"))
      (node (ref "IC6") (pin "5") (pinfunction "V+_5") (pintype "power_in"))
      (node (ref "IC7") (pin "6") (pinfunction "VCC_6") (pintype "passive"))
      (node (ref "IC8") (pin "17") (pinfunction "VDD_2_17") (pintype "passive"))
      (node (ref "IC8") (pin "48") (pinfunction "VDD_1_48") (pintype "bidirectional"))
      (node (ref "JP1") (pin "1") (pinfunction "1_1") (pintype "passive"))
      (node (ref "JP2") (pin "1") (pinfunction "1_1") (pintype "passive"))
      (node (ref "NTC1") (pin "1") (pinfunction "P$1_1") (pintype "bidirectional"))
      (node (ref "NTC2") (pin "1") (pinfunction "P$1_1") (pintype "bidirectional"))
      (node (ref "Q10") (pin "2") (pinfunction "S_2") (pintype "passive"))
      (node (ref "Q5") (pin "2") (pinfunction "S_2") (pintype "passive"))
      (node (ref "R20") (pin "1") (pinfunction "1_1") (pintype "passive"))
      (node (ref "R23") (pin "1") (pinfunction "1_1") (pintype "passive"))
    )
    (net (code "2") (name "+8V") (class "Default")
      (node (ref "C14") (pin "1") (pinfunction "1_1") (pintype "passive"))
      (node (ref "C22") (pin "2") (pinfunction "2_2") (pintype "passive"))
      (node (ref "C45") (pin "1") (pinfunction "1_1") (pintype "passive"))
      (node (ref "D10") (pin "A") (pinfunction "A_A") (pintype "passive"))
      (node (ref "D5") (pin "A") (pinfunction "A_A") (pintype "passive"))
      (node (ref "IC10") (pin "8") (pinfunction "V+_8") (pintype "power_in"))
      (node (ref "IC5") (pin "1") (pinfunction "IN_1") (pintype "input"))
      (node (ref "IC5") (pin "3") (pinfunction "ON/~{OFF}_3") (pintype "input"))
      (node (ref "R4") (pin "1") (pinfunction "1_1") (pintype "passive"))
    )
    (net (code "3") (name "+VAUX") (class "Default")
      (node (ref "X2") (pin "2") (pinfunction "1_2") (pintype "passive"))
    )
    (net (code "4") (name "+VREF") (class "Default")
      (node (ref "C39") (pin "2") (pinfunction "2_2") (pintype "passive"))
      (node (ref "IC8") (pin "25") (pinfunction "VREFSD+_25") (pintype "passive"))
      (node (ref "IC8") (pin "9") (pinfunction "VDDA/VREF+_9") (pintype "passive"))
      (node (ref "IC9") (pin "1") (pinfunction "C_1") (pintype "passive"))
      (node (ref "IC9") (pin "2") (pinfunction "R_2") (pintype "passive"))
      (node (ref "R23") (pin "2") (pinfunction "2_2") (pintype "passive"))
    )
    (net (code "5") (name "-8V") (class "Default")
      (node (ref "C5") (pin "1") (pinfunction "1_1") (pintype "passive"))
      (node (ref "C51") (pin "2") (pinfunction "2_2") (pintype "passive"))
      (node (ref "IC10") (pin "4") (pinfunction "V-_4") (pintype "power_in"))
      (node (ref "R2") (pin "1") (pinfunction "1_1") (pintype "passive"))
    )
    (net (code "6") (name "AGND") (class "Default")
      (node (ref "C39") (pin "1") (pinfunction "1_1") (pintype "passive"))
      (node (ref "IC8") (pin "23") (pinfunction "VSSSD/VREFSD-_23") (pintype "passive"))
      (node (ref "IC8") (pin "8") (pinfunction "VSSA/VREF-_8") (pintype "passive"))
      (node (ref "IC9") (pin "3") (pinfunction "A_3") (pintype "passive"))
      (node (ref "SH2") (pin "1") (pinfunction "GND_A_1") (pintype "bidirectional"))
    )
    (net (code "7") (name "BOOT0") (class "Default")
      (node (ref "IC3") (pin "13") (pinfunction "B2_13") (pintype "output"))
      (node (ref "IC8") (pin "44") (pinfunction "BOOT0_44") (pintype "input"))
      (node (ref "JP1") (pin "2") (pinfunction "2_2") (pintype "passive"))
      (node (ref "R15") (pin "2") (pinfunction "2_2") (pintype "passive"))
    )
    (net (code "8") (name "CC#1") (class "Default")
      (node (ref "IC12") (pin "7") (pinfunction "OUT_7") (pintype "output"))
      (node (ref "IC8") (pin "3") (pinfunction "PC14-OSC32_IN_3") (pintype "bidirectional"))
    )
    (net (code "9") (name "CC#2") (class "Default")
      (node (ref "IC12") (pin "1") (pinfunction "OUT_1") (pintype "output"))
      (node (ref "IC8") (pin "4") (pinfunction "PC15-OSC32_OUT_4") (pintype "bidirectional"))
    )
    (net (code "10") (name "CC_LED#1") (class "Default")
      (node (ref "IC8") (pin "2") (pinfunction "PC13_2") (pintype "bidirectional"))
      (node (ref "Q5") (pin "1") (pinfunction "G_1") (pintype "passive"))
      (node (ref "R49") (pin "2") (pinfunction "2_2") (pintype "passive"))
    )
    (net (code "11") (name "CC_LED#2") (class "Default")
      (node (ref "IC8") (pin "11") (pinfunction "PA1_11") (pintype "bidirectional"))
      (node (ref "Q10") (pin "1") (pinfunction "G_1") (pintype "passive"))
      (node (ref "R73") (pin "2") (pinfunction "2_2") (pintype "passive"))
    )
    (net (code "12") (name "DC_OUT+") (class "Default")
      (node (ref "C3") (pin "2") (pinfunction "2_2") (pintype "passive"))
      (node (ref "C46") (pin "+") (pinfunction "+_+") (pintype "passive"))
      (node (ref "C50") (pin "1") (pinfunction "1_1") (pintype "passive"))
      (node (ref "C52") (pin "1") (pinfunction "1_1") (pintype "passive"))
      (node (ref "C6") (pin "1") (pinfunction "1_1") (pintype "passive"))
      (node (ref "C68") (pin "+") (pinfunction "+_+") (pintype "passive"))
      (node (ref "C71") (pin "1") (pinfunction "1_1") (pintype "passive"))
      (node (ref "C72") (pin "1") (pinfunction "1_1") (pintype "passive"))
      (node (ref "C9") (pin "1") (pinfunction "1_1") (pintype "passive"))
      (node (ref "IC11") (pin "6") (pinfunction "IVINN_6") (pintype "input"))
      (node (ref "IC11") (pin "7") (pinfunction "IVINP_7") (pintype "input"))
      (node (ref "IC13") (pin "6") (pinfunction "IVINN_6") (pintype "input"))
      (node (ref "IC13") (pin "7") (pinfunction "IVINP_7") (pintype "input"))
      (node (ref "IC2") (pin "2") (pinfunction "VIN_2") (pintype "power_in"))
      (node (ref "L1") (pin "4") (pinfunction "2_4") (pintype "passive"))
      (node (ref "Q2") (pin "2") (pinfunction "D_2") (pintype "passive"))
      (node (ref "Q7") (pin "2") (pinfunction "D_2") (pintype "passive"))
      (node (ref "R28") (pin "1") (pinfunction "1_1") (pintype "passive"))
      (node (ref "R29") (pin "1") (pinfunction "1_1") (pintype "passive"))
      (node (ref "R3") (pin "2") (pinfunction "2_2") (pintype "passive"))
      (node (ref "R52") (pin "1") (pinfunction "1_1") (pintype "passive"))
      (node (ref "R53") (pin "1") (pinfunction "1_1") (pintype "passive"))
      (node (ref "ZD1") (pin "C") (pinfunction "C_C") (pintype "passive"))
    )
    (net (code "13") (name "DIB_5V") (class "Default")
      (node (ref "X2") (pin "23") (pinfunction "1_23") (pintype "passive"))
      (node (ref "X2") (pin "24") (pinfunction "1_24") (pintype "passive"))
    )
    (net (code "14") (name "DIB_12V") (class "Default")
      (node (ref "X2") (pin "21") (pinfunction "1_21") (pintype "passive"))
      (node (ref "X2") (pin "22") (pinfunction "1_22") (pintype "passive"))
    )
    (net (code "15") (name "DIB_A0") (class "Default")
      (node (ref "IC4") (pin "1") (pinfunction "A0_1") (pintype "input"))
      (node (ref "R13") (pin "2") (pinfunction "2_2") (pintype "passive"))
      (node (ref "X2") (pin "17") (pinfunction "1_17") (pintype "passive"))
    )
    (net (code "16") (name "DIB_A1") (class "Default")
      (node (ref "IC4") (pin "2") (pinfunction "A1_2") (pintype "input"))
      (node (ref "R12") (pin "2") (pinfunction "2_2") (pintype "passive"))
      (node (ref "X2") (pin "19") (pinfunction "1_19") (pintype "passive"))
    )
    (net (code "17") (name "DIB_A2") (class "Default")
      (node (ref "IC4") (pin "3") (pinfunction "A2_3") (pintype "input"))
      (node (ref "R11") (pin "2") (pinfunction "2_2") (pintype "passive"))
      (node (ref "X2") (pin "18") (pinfunction "1_18") (pintype "passive"))
    )
    (net (code "18") (name "DIB_BOOT0") (class "Default")
      (node (ref "IC3") (pin "4") (pinfunction "A2_4") (pintype "input"))
      (node (ref "X2") (pin "26") (pinfunction "1_26") (pintype "passive"))
    )
    (net (code "19") (name "DIB_CSA") (class "Default")
      (node (ref "IC1") (pin "5") (pinfunction "A4_5") (pintype "input"))
      (node (ref "X2") (pin "9") (pinfunction "1_9") (pintype "passive"))
    )
    (net (code "20") (name "DIB_CSB") (class "Default")
      (node (ref "X2") (pin "12") (pinfunction "1_12") (pintype "passive"))
    )
    (net (code "21") (name "DIB_IRQ") (class "Default")
      (node (ref "IC1") (pin "7") (pinfunction "A6_7") (pintype "output"))
      (node (ref "X2") (pin "10") (pinfunction "1_10") (pintype "passive"))
    )
    (net (code "22") (name "DIB_MISO") (class "Default")
      (node (ref "IC1") (pin "6") (pinfunction "A5_6") (pintype "output"))
      (node (ref "X2") (pin "14") (pinfunction "1_14") (pintype "passive"))
    )
    (net (code "23") (name "DIB_MOSI") (class "Default")
      (node (ref "IC3") (pin "3") (pinfunction "A1_3") (pintype "input"))
      (node (ref "X2") (pin "15") (pinfunction "1_15") (pintype "passive"))
    )
    (net (code "24") (name "DIB_NFAULT") (class "Default")
      (node (ref "X2") (pin "3") (pinfunction "1_3") (pintype "passive"))
    )
    (net (code "25") (name "DIB_NRESET") (class "Default")
      (node (ref "IC1") (pin "2") (pinfunction "A1_2") (pintype "input"))
      (node (ref "X2") (pin "4") (pinfunction "1_4") (pintype "passive"))
    )
    (net (code "26") (name "DIB_SCL") (class "Default")
      (node (ref "IC4") (pin "6") (pinfunction "SCL_6") (pintype "bidirectional"))
      (node (ref "X2") (pin "5") (pinfunction "1_5") (pintype "passive"))
    )
    (net (code "27") (name "DIB_SCLK") (class "Default")
      (node (ref "IC1") (pin "4") (pinfunction "A3_4") (pintype "input"))
      (node (ref "X2") (pin "13") (pinfunction "1_13") (pintype "passive"))
    )
    (net (code "28") (name "DIB_SDA") (class "Default")
      (node (ref "IC4") (pin "5") (pinfunction "SDA_5") (pintype "bidirectional"))
      (node (ref "X2") (pin "8") (pinfunction "1_8") (pintype "passive"))
    )
    (net (code "29") (name "DIB_SYNC") (class "Default")
      (node (ref "IC1") (pin "3") (pinfunction "A2_3") (pintype "input"))
      (node (ref "X2") (pin "6") (pinfunction "1_6") (pintype "passive"))
    )
    (net (code "30") (name "DIB_UART_RX") (class "Default")
      (node (ref "IC3") (pin "6") (pinfunction "A4_6") (pintype "output"))
      (node (ref "X2") (pin "28") (pinfunction "1_28") (pintype "passive"))
    )
    (net (code "31") (name "DIB_UART_TX") (class "Default")
      (node (ref "IC3") (pin "5") (pinfunction "A3_5") (pintype "input"))
      (node (ref "X2") (pin "27") (pinfunction "1_27") (pintype "passive"))
    )
    (net (code "32") (name "FB1") (class "Default")
      (node (ref "IC11") (pin "11") (pinfunction "FB_11") (pintype "input"))
      (node (ref "IC12") (pin "10") (pinfunction "+IN_10") (pintype "input"))
      (node (ref "R39") (pin "1") (pinfunction "1_1") (pintype "passive"))
      (node (ref "R46") (pin "2") (pinfunction "2_2") (pintype "passive"))
      (node (ref "R48") (pin "2") (pinfunction "2_2") (pintype "passive"))
    )
    (net (code "33") (name "FB2") (class "Default")
      (node (ref "IC12") (pin "12") (pinfunction "+IN_12") (pintype "input"))
      (node (ref "IC13") (pin "11") (pinfunction "FB_11") (pintype "input"))
      (node (ref "R63") (pin "1") (pinfunction "1_1") (pintype "passive"))
      (node (ref "R70") (pin "2") (pinfunction "2_2") (pintype "passive"))
      (node (ref "R72") (pin "2") (pinfunction "2_2") (pintype "passive"))
    )
    (net (code "34") (name "GND") (class "Default")
      (node (ref "C12") (pin "2") (pinfunction "2_2") (pintype "passive"))
      (node (ref "C13") (pin "2") (pinfunction "2_2") (pintype "passive"))
      (node (ref "C14") (pin "2") (pinfunction "2_2") (pintype "passive"))
      (node (ref "C15") (pin "2") (pinfunction "2_2") (pintype "passive"))
      (node (ref "C16") (pin "1") (pinfunction "1_1") (pintype "passive"))
      (node (ref "C18") (pin "1") (pinfunction "1_1") (pintype "passive"))
      (node (ref "C19") (pin "1") (pinfunction "1_1") (pintype "passive"))
      (node (ref "C2") (pin "1") (pinfunction "1_1") (pintype "passive"))
      (node (ref "C21") (pin "2") (pinfunction "2_2") (pintype "passive"))
      (node (ref "C22") (pin "1") (pinfunction "1_1") (pintype "passive"))
      (node (ref "C23") (pin "1") (pinfunction "1_1") (pintype "passive"))
      (node (ref "C25") (pin "2") (pinfunction "2_2") (pintype "passive"))
      (node (ref "C26") (pin "2") (pinfunction "2_2") (pintype "passive"))
      (node (ref "C27") (pin "2") (pinfunction "2_2") (pintype "passive"))
      (node (ref "C28") (pin "1") (pinfunction "1_1") (pintype "passive"))
      (node (ref "C29") (pin "2") (pinfunction "2_2") (pintype "passive"))
      (node (ref "C31") (pin "2") (pinfunction "2_2") (pintype "passive"))
      (node (ref "C32") (pin "1") (pinfunction "1_1") (pintype "passive"))
      (node (ref "C33") (pin "1") (pinfunction "1_1") (pintype "passive"))
      (node (ref "C34") (pin "1") (pinfunction "1_1") (pintype "passive"))
      (node (ref "C35") (pin "1") (pinfunction "1_1") (pintype "passive"))
      (node (ref "C37") (pin "1") (pinfunction "1_1") (pintype "passive"))
      (node (ref "C38") (pin "1") (pinfunction "1_1") (pintype "passive"))
      (node (ref "C4") (pin "2") (pinfunction "2_2") (pintype "passive"))
      (node (ref "C40") (pin "1") (pinfunction "1_1") (pintype "passive"))
      (node (ref "C41") (pin "1") (pinfunction "1_1") (pintype "passive"))
      (node (ref "C42") (pin "1") (pinfunction "1_1") (pintype "passive"))
      (node (ref "C43") (pin "1") (pinfunction "1_1") (pintype "passive"))
      (node (ref "C44") (pin "1") (pinfunction "1_1") (pintype "passive"))
      (node (ref "C45") (pin "2") (pinfunction "2_2") (pintype "passive"))
      (node (ref "C46") (pin "-") (pinfunction "-_-") (pintype "passive"))
      (node (ref "C47") (pin "2") (pinfunction "2_2") (pintype "passive"))
      (node (ref "C49") (pin "2") (pinfunction "2_2") (pintype "passive"))
      (node (ref "C5") (pin "2") (pinfunction "2_2") (pintype "passive"))
      (node (ref "C50") (pin "2") (pinfunction "2_2") (pintype "passive"))
      (node (ref "C51") (pin "1") (pinfunction "1_1") (pintype "passive"))
      (node (ref "C52") (pin "2") (pinfunction "2_2") (pintype "passive"))
      (node (ref "C53") (pin "2") (pinfunction "2_2") (pintype "passive"))
      (node (ref "C55") (pin "2") (pinfunction "2_2") (pintype "passive"))
      (node (ref "C57") (pin "2") (pinfunction "2_2") (pintype "passive"))
      (node (ref "C59") (pin "2") (pinfunction "2_2") (pintype "passive"))
      (node (ref "C6") (pin "2") (pinfunction "2_2") (pintype "passive"))
      (node (ref "C60") (pin "2") (pinfunction "2_2") (pintype "passive"))
      (node (ref "C61") (pin "2") (pinfunction "-_2") (pintype "passive"))
      (node (ref "C62") (pin "-") (pinfunction "-_-") (pintype "passive"))
      (node (ref "C63") (pin "2") (pinfunction "2_2") (pintype "passive"))
      (node (ref "C64") (pin "1") (pinfunction "1_1") (pintype "passive"))
      (node (ref "C66") (pin "1") (pinfunction "1_1") (pintype "passive"))
      (node (ref "C68") (pin "-") (pinfunction "-_-") (pintype "passive"))
      (node (ref "C70") (pin "2") (pinfunction "2_2") (pintype "passive"))
      (node (ref "C71") (pin "2") (pinfunction "2_2") (pintype "passive"))
      (node (ref "C72") (pin "2") (pinfunction "2_2") (pintype "passive"))
      (node (ref "C73") (pin "2") (pinfunction "2_2") (pintype "passive"))
      (node (ref "C75") (pin "2") (pinfunction "2_2") (pintype "passive"))
      (node (ref "C77") (pin "2") (pinfunction "2_2") (pintype "passive"))
      (node (ref "C79") (pin "2") (pinfunction "2_2") (pintype "passive"))
      (node (ref "C8") (pin "1") (pinfunction "1_1") (pintype "passive"))
      (node (ref "C80") (pin "2") (pinfunction "2_2") (pintype "passive"))
      (node (ref "C81") (pin "2") (pinfunction "-_2") (pintype "passive"))
      (node (ref "C82") (pin "-") (pinfunction "-_-") (pintype "passive"))
      (node (ref "C83") (pin "2") (pinfunction "2_2") (pintype "passive"))
      (node (ref "C84") (pin "1") (pinfunction "1_1") (pintype "passive"))
      (node (ref "C86") (pin "1") (pinfunction "1_1") (pintype "passive"))
      (node (ref "C9") (pin "2") (pinfunction "2_2") (pintype "passive"))
      (node (ref "CH1") (pin "GND") (pinfunction "GND_GND") (pintype "bidirectional"))
      (node (ref "CH2") (pin "GND") (pinfunction "GND_GND") (pintype "bidirectional"))
      (node (ref "D12") (pin "A") (pinfunction "A_A") (pintype "passive"))
      (node (ref "D2") (pin "A") (pinfunction "A_A") (pintype "passive"))
      (node (ref "D7") (pin "A") (pinfunction "A_A") (pintype "passive"))
      (node (ref "GND") (pin "1") (pinfunction "P$1_1") (pintype "bidirectional"))
      (node (ref "IC1") (pin "9") (pinfunction "GND2_9") (pintype "passive"))
      (node (ref "IC11") (pin "12") (pinfunction "GND_12") (pintype "passive"))
      (node (ref "IC11") (pin "21") (pinfunction "SYNC_21") (pintype "input"))
      (node (ref "IC11") (pin "23") (pinfunction "GND_23") (pintype "passive"))
      (node (ref "IC11") (pin "28") (pinfunction "GND_28") (pintype "passive"))
      (node (ref "IC11") (pin "TP") (pinfunction "GND_PAD_TP") (pintype "passive"))
      (node (ref "IC12") (pin "11") (pinfunction "V-_11") (pintype "power_in"))
      (node (ref "IC13") (pin "12") (pinfunction "GND_12") (pintype "passive"))
      (node (ref "IC13") (pin "21") (pinfunction "SYNC_21") (pintype "input"))
      (node (ref "IC13") (pin "23") (pinfunction "GND_23") (pintype "passive"))
      (node (ref "IC13") (pin "28") (pinfunction "GND_28") (pintype "passive"))
      (node (ref "IC13") (pin "TP") (pinfunction "GND_PAD_TP") (pintype "passive"))
      (node (ref "IC2") (pin "9") (pinfunction "GND_9") (pintype "passive"))
      (node (ref "IC2") (pin "TP") (pinfunction "TP_TP") (pintype "passive"))
      (node (ref "IC3") (pin "15") (pinfunction "GND2_15") (pintype "passive"))
      (node (ref "IC3") (pin "9") (pinfunction "GND2_2_9") (pintype "passive"))
      (node (ref "IC5") (pin "2") (pinfunction "GND_2") (pintype "passive"))
      (node (ref "IC6") (pin "2") (pinfunction "V-_2") (pintype "power_in"))
      (node (ref "IC7") (pin "3") (pinfunction "GND_3") (pintype "power_in"))
      (node (ref "IC8") (pin "47") (pinfunction "VSS_1_47") (pintype "bidirectional"))
      (node (ref "J3") (pin "1") (pinfunction "1_1") (pintype "passive"))
      (node (ref "J3") (pin "1.1") (pinfunction "1_1.1") (pintype "passive"))
      (node (ref "J5") (pin "1") (pinfunction "1_1") (pintype "passive"))
      (node (ref "J5") (pin "1.1") (pinfunction "1_1.1") (pintype "passive"))
      (node (ref "L1") (pin "2") (pinfunction "2_2") (pintype "passive"))
      (node (ref "LED1") (pin "CC") (pinfunction "C_CC") (pintype "passive"))
      (node (ref "LED2") (pin "CC") (pinfunction "C_CC") (pintype "passive"))
      (node (ref "Q3") (pin "3") (pinfunction "S_3") (pintype "passive"))
      (node (ref "Q8") (pin "3") (pinfunction "S_3") (pintype "passive"))
      (node (ref "R10") (pin "1") (pinfunction "1_1") (pintype "passive"))
      (node (ref "R15") (pin "1") (pinfunction "1_1") (pintype "passive"))
      (node (ref "R19") (pin "1") (pinfunction "1_1") (pintype "passive"))
      (node (ref "R21") (pin "2") (pinfunction "2_2") (pintype "passive"))
      (node (ref "R22") (pin "2") (pinfunction "2_2") (pintype "passive"))
      (node (ref "R30") (pin "1") (pinfunction "1_1") (pintype "passive"))
      (node (ref "R33") (pin "1") (pinfunction "1_1") (pintype "passive"))
      (node (ref "R37") (pin "1") (pinfunction "1_1") (pintype "passive"))
      (node (ref "R41") (pin "2") (pinfunction "2_2") (pintype "passive"))
      (node (ref "R42") (pin "1") (pinfunction "1_1") (pintype "passive"))
      (node (ref "R45") (pin "1") (pinfunction "1_1") (pintype "passive"))
      (node (ref "R46") (pin "1") (pinfunction "1_1") (pintype "passive"))
      (node (ref "R47") (pin "1") (pinfunction "1_1") (pintype "passive"))
      (node (ref "R5") (pin "1") (pinfunction "1_1") (pintype "passive"))
      (node (ref "R51") (pin "1") (pinfunction "1_1") (pintype "passive"))
      (node (ref "R54") (pin "1") (pinfunction "1_1") (pintype "passive"))
      (node (ref "R57") (pin "1") (pinfunction "1_1") (pintype "passive"))
      (node (ref "R6") (pin "1") (pinfunction "1_1") (pintype "passive"))
      (node (ref "R61") (pin "1") (pinfunction "1_1") (pintype "passive"))
      (node (ref "R65") (pin "2") (pinfunction "2_2") (pintype "passive"))
      (node (ref "R66") (pin "1") (pinfunction "1_1") (pintype "passive"))
      (node (ref "R69") (pin "1") (pinfunction "1_1") (pintype "passive"))
      (node (ref "R70") (pin "1") (pinfunction "1_1") (pintype "passive"))
      (node (ref "R71") (pin "1") (pinfunction "1_1") (pintype "passive"))
      (node (ref "R75") (pin "1") (pinfunction "1_1") (pintype "passive"))
      (node (ref "R8") (pin "1") (pinfunction "1_1") (pintype "passive"))
      (node (ref "SH2") (pin "2") (pinfunction "GND_B_2") (pintype "bidirectional"))
      (node (ref "TR1") (pin "4") (pinfunction "4_4") (pintype "passive"))
      (node (ref "X3") (pin "3") (pinfunction "S_3") (pintype "passive"))
      (node (ref "X4") (pin "1") (pinfunction "1_1") (pintype "passive"))
      (node (ref "X4") (pin "10") (pinfunction "1_10") (pintype "passive"))
      (node (ref "X4") (pin "2") (pinfunction "1_2") (pintype "passive"))
      (node (ref "X4") (pin "3") (pinfunction "1_3") (pintype "passive"))
      (node (ref "X4") (pin "4") (pinfunction "1_4") (pintype "passive"))
      (node (ref "X4") (pin "5") (pinfunction "1_5") (pintype "passive"))
      (node (ref "X4") (pin "6") (pinfunction "1_6") (pintype "passive"))
      (node (ref "X4") (pin "7") (pinfunction "1_7") (pintype "passive"))
      (node (ref "X4") (pin "8") (pinfunction "1_8") (pintype "passive"))
      (node (ref "X4") (pin "9") (pinfunction "1_9") (pintype "passive"))
      (node (ref "ZD1") (pin "A") (pinfunction "A_A") (pintype "passive"))
      (node (ref "ZD3") (pin "A") (pinfunction "A_A") (pintype "passive"))
      (node (ref "ZD5") (pin "A") (pinfunction "A_A") (pintype "passive"))
    )
    (net (code "35") (name "GNDIO") (class "Default")
      (node (ref "C17") (pin "2") (pinfunction "2_2") (pintype "passive"))
      (node (ref "C20") (pin "1") (pinfunction "1_1") (pintype "passive"))
      (node (ref "C7") (pin "2") (pinfunction "2_2") (pintype "passive"))
      (node (ref "IC1") (pin "8") (pinfunction "GND1_8") (pintype "passive"))
      (node (ref "IC3") (pin "2") (pinfunction "GND1_2_2") (pintype "passive"))
      (node (ref "IC3") (pin "8") (pinfunction "GND1_8") (pintype "passive"))
      (node (ref "IC4") (pin "4") (pinfunction "GND_4") (pintype "passive"))
      (node (ref "IC4") (pin "7") (pinfunction "WP_7") (pintype "input"))
      (node (ref "X2") (pin "11") (pinfunction "1_11") (pintype "passive"))
      (node (ref "X2") (pin "16") (pinfunction "1_16") (pintype "passive"))
      (node (ref "X2") (pin "20") (pinfunction "1_20") (pintype "passive"))
      (node (ref "X2") (pin "25") (pinfunction "1_25") (pintype "passive"))
      (node (ref "X2") (pin "7") (pinfunction "1_7") (pintype "passive"))
    )
    (net (code "36") (name "INTVCC1") (class "Default")
      (node (ref "C55") (pin "1") (pinfunction "1_1") (pintype "passive"))
      (node (ref "D6") (pin "A") (pinfunction "A_A") (pintype "passive"))
      (node (ref "IC11") (pin "2") (pinfunction "INTVCC_2") (pintype "passive"))
      (node (ref "R43") (pin "1") (pinfunction "1_1") (pintype "passive"))
      (node (ref "R44") (pin "2") (pinfunction "2_2") (pintype "passive"))
    )
    (net (code "37") (name "INTVCC2") (class "Default")
      (node (ref "C75") (pin "1") (pinfunction "1_1") (pintype "passive"))
      (node (ref "D11") (pin "A") (pinfunction "A_A") (pintype "passive"))
      (node (ref "IC13") (pin "2") (pinfunction "INTVCC_2") (pintype "passive"))
      (node (ref "R67") (pin "1") (pinfunction "1_1") (pintype "passive"))
      (node (ref "R68") (pin "2") (pinfunction "2_2") (pintype "passive"))
    )
    (net (code "38") (name "IRQ") (class "Default")
      (node (ref "IC1") (pin "10") (pinfunction "B6_10") (pintype "input"))
      (node (ref "IC8") (pin "33") (pinfunction "PA12_33") (pintype "bidirectional"))
    )
    (net (code "39") (name "I_MON#1") (class "Default")
      (node (ref "C42") (pin "2") (pinfunction "2_2") (pintype "passive"))
      (node (ref "IC8") (pin "19") (pinfunction "PB1_19") (pintype "bidirectional"))
      (node (ref "R25") (pin "1") (pinfunction "1_1") (pintype "passive"))
    )
    (net (code "40") (name "I_MON#2") (class "Default")
      (node (ref "C44") (pin "2") (pinfunction "2_2") (pintype "passive"))
      (node (ref "IC8") (pin "21") (pinfunction "PE8_21") (pintype "bidirectional"))
      (node (ref "R27") (pin "1") (pinfunction "1_1") (pintype "passive"))
    )
    (net (code "41") (name "I_MON1") (class "Default")
      (node (ref "C64") (pin "2") (pinfunction "2_2") (pintype "passive"))
      (node (ref "R25") (pin "2") (pinfunction "2_2") (pintype "passive"))
      (node (ref "R38") (pin "1") (pinfunction "1_1") (pintype "passive"))
    )
    (net (code "42") (name "I_MON2") (class "Default")
      (node (ref "C84") (pin "2") (pinfunction "2_2") (pintype "passive"))
      (node (ref "R27") (pin "2") (pinfunction "2_2") (pintype "passive"))
      (node (ref "R62") (pin "1") (pinfunction "1_1") (pintype "passive"))
    )
    (net (code "43") (name "I_SET#1") (class "Default")
      (node (ref "I_SET1") (pin "1") (pinfunction "1_1") (pintype "passive"))
      (node (ref "R32") (pin "1") (pinfunction "1_1") (pintype "passive"))
    )
    (net (code "44") (name "I_SET#2") (class "Default")
      (node (ref "I_SET2") (pin "1") (pinfunction "1_1") (pintype "passive"))
      (node (ref "R56") (pin "1") (pinfunction "1_1") (pintype "passive"))
    )
    (net (code "45") (name "I_SET_OUT#1") (class "Default")
      (node (ref "IC6") (pin "1") (pinfunction "I_1") (pintype "input"))
      (node (ref "IC8") (pin "45") (pinfunction "PB8_45") (pintype "bidirectional"))
      (node (ref "R14") (pin "2") (pinfunction "2_2") (pintype "passive"))
    )
    (net (code "46") (name "I_SET_OUT#2") (class "Default")
      (node (ref "IC6") (pin "3") (pinfunction "I_3") (pintype "input"))
      (node (ref "IC8") (pin "46") (pinfunction "PB9_46") (pintype "bidirectional"))
      (node (ref "R17") (pin "2") (pinfunction "2_2") (pintype "passive"))
    )
    (net (code "47") (name "MISO") (class "Default")
      (node (ref "IC1") (pin "11") (pinfunction "B5_11") (pintype "input"))
      (node (ref "IC8") (pin "30") (pinfunction "PA9_30") (pintype "bidirectional"))
    )
    (net (code "48") (name "MOSI") (class "Default")
      (node (ref "IC8") (pin "31") (pinfunction "PA10_31") (pintype "bidirectional"))
      (node (ref "RN1") (pin "5") (pinfunction "2_5") (pintype "passive"))
    )
    (net (code "49") (name "NRST") (class "Default")
      (node (ref "C36") (pin "1") (pinfunction "1_1") (pintype "passive"))
      (node (ref "IC8") (pin "7") (pinfunction "NRST_7") (pintype "input"))
      (node (ref "JP3") (pin "2") (pinfunction "2_2") (pintype "passive"))
      (node (ref "R20") (pin "2") (pinfunction "2_2") (pintype "passive"))
      (node (ref "RN2") (pin "3") (pinfunction "1_3") (pintype "passive"))
    )
    (net (code "50") (name "NSS") (class "Default")
      (node (ref "IC8") (pin "32") (pinfunction "PA11_32") (pintype "bidirectional"))
      (node (ref "RN1") (pin "6") (pinfunction "2_6") (pintype "passive"))
    )
    (net (code "51") (name "Net-(C4-Pad1)") (class "Default")
      (node (ref "C4") (pin "1") (pinfunction "1_1") (pintype "passive"))
      (node (ref "D1") (pin "A") (pinfunction "A_A") (pintype "passive"))
      (node (ref "R2") (pin "2") (pinfunction "2_2") (pintype "passive"))
    )
    (net (code "52") (name "Net-(C11-Pad2)") (class "Default")
      (node (ref "C11") (pin "2") (pinfunction "2_2") (pintype "passive"))
      (node (ref "R5") (pin "2") (pinfunction "2_2") (pintype "passive"))
    )
    (net (code "53") (name "Net-(C12-Pad1)") (class "Default")
      (node (ref "C12") (pin "1") (pinfunction "1_1") (pintype "passive"))
      (node (ref "C13") (pin "1") (pinfunction "1_1") (pintype "passive"))
      (node (ref "R4") (pin "2") (pinfunction "2_2") (pintype "passive"))
      (node (ref "R7") (pin "2") (pinfunction "2_2") (pintype "passive"))
      (node (ref "TR1") (pin "3") (pinfunction "3_3") (pintype "passive"))
    )
    (net (code "54") (name "Net-(C19-Pad2)") (class "Default")
      (node (ref "C19") (pin "2") (pinfunction "2_2") (pintype "passive"))
      (node (ref "R9") (pin "1") (pinfunction "1_1") (pintype "passive"))
    )
    (net (code "55") (name "Net-(C24-Pad1)") (class "Default")
      (node (ref "C24") (pin "1") (pinfunction "1_1") (pintype "passive"))
      (node (ref "C26") (pin "1") (pinfunction "1_1") (pintype "passive"))
      (node (ref "I_SET1") (pin "2") (pinfunction "2_2") (pintype "passive"))
      (node (ref "R14") (pin "1") (pinfunction "1_1") (pintype "passive"))
    )
    (net (code "56") (name "Net-(C24-Pad2)") (class "Default")
      (node (ref "C24") (pin "2") (pinfunction "2_2") (pintype "passive"))
      (node (ref "R16") (pin "1") (pinfunction "1_1") (pintype "passive"))
    )
    (net (code "57") (name "Net-(C30-Pad1)") (class "Default")
      (node (ref "C30") (pin "1") (pinfunction "1_1") (pintype "passive"))
      (node (ref "C31") (pin "1") (pinfunction "1_1") (pintype "passive"))
      (node (ref "I_SET2") (pin "2") (pinfunction "2_2") (pintype "passive"))
      (node (ref "R17") (pin "1") (pinfunction "1_1") (pintype "passive"))
    )
    (net (code "58") (name "Net-(C30-Pad2)") (class "Default")
      (node (ref "C30") (pin "2") (pinfunction "2_2") (pintype "passive"))
      (node (ref "R18") (pin "1") (pinfunction "1_1") (pintype "passive"))
    )
    (net (code "59") (name "Net-(C58-Pad2)") (class "Default")
      (node (ref "C58") (pin "2") (pinfunction "2_2") (pintype "passive"))
      (node (ref "R37") (pin "2") (pinfunction "2_2") (pintype "passive"))
    )
    (net (code "60") (name "Net-(C67-Pad1)") (class "Default")
      (node (ref "C67") (pin "1") (pinfunction "1_1") (pintype "passive"))
      (node (ref "R45") (pin "2") (pinfunction "2_2") (pintype "passive"))
    )
    (net (code "61") (name "Net-(C78-Pad2)") (class "Default")
      (node (ref "C78") (pin "2") (pinfunction "2_2") (pintype "passive"))
      (node (ref "R61") (pin "2") (pinfunction "2_2") (pintype "passive"))
    )
    (net (code "62") (name "Net-(C87-Pad1)") (class "Default")
      (node (ref "C87") (pin "1") (pinfunction "1_1") (pintype "passive"))
      (node (ref "R69") (pin "2") (pinfunction "2_2") (pintype "passive"))
    )
    (net (code "63") (name "Net-(D1-PadC)") (class "Default")
      (node (ref "D1") (pin "C") (pinfunction "C_C") (pintype "passive"))
      (node (ref "TR1") (pin "2") (pinfunction "2_2") (pintype "passive"))
    )
    (net (code "64") (name "Net-(IC1-B2)") (class "Default")
      (node (ref "IC1") (pin "14") (pinfunction "B2_14") (pintype "output"))
      (node (ref "RN1") (pin "1") (pinfunction "1_1") (pintype "passive"))
    )
    (net (code "65") (name "Net-(IC1-B3)") (class "Default")
      (node (ref "IC1") (pin "13") (pinfunction "B3_13") (pintype "output"))
      (node (ref "RN1") (pin "2") (pinfunction "1_2") (pintype "passive"))
    )
    (net (code "66") (name "Net-(IC1-B4)") (class "Default")
      (node (ref "IC1") (pin "12") (pinfunction "B4_12") (pintype "output"))
      (node (ref "RN1") (pin "3") (pinfunction "1_3") (pintype "passive"))
    )
    (net (code "67") (name "Net-(IC2-BOOT)") (class "Default")
      (node (ref "C10") (pin "2") (pinfunction "2_2") (pintype "passive"))
      (node (ref "IC2") (pin "1") (pinfunction "BOOT_1") (pintype "output"))
    )
    (net (code "68") (name "Net-(IC2-COMP)") (class "Default")
      (node (ref "C16") (pin "2") (pinfunction "2_2") (pintype "passive"))
      (node (ref "IC2") (pin "8") (pinfunction "COMP_8") (pintype "output"))
      (node (ref "R9") (pin "2") (pinfunction "2_2") (pintype "passive"))
    )
    (net (code "69") (name "Net-(IC2-EN)") (class "Default")
      (node (ref "IC2") (pin "3") (pinfunction "EN_3") (pintype "input"))
      (node (ref "R3") (pin "1") (pinfunction "1_1") (pintype "passive"))
      (node (ref "R6") (pin "2") (pinfunction "2_2") (pintype "passive"))
    )
    (net (code "70") (name "Net-(IC2-PH)") (class "Default")
      (node (ref "C10") (pin "1") (pinfunction "1_1") (pintype "passive"))
      (node (ref "C11") (pin "1") (pinfunction "1_1") (pintype "passive"))
      (node (ref "D2") (pin "C") (pinfunction "C_C") (pintype "passive"))
      (node (ref "IC2") (pin "10") (pinfunction "PH_10") (pintype "input"))
      (node (ref "TR1") (pin "1") (pinfunction "1_1") (pintype "passive"))
    )
    (net (code "71") (name "Net-(IC2-RT{slash}CLK)") (class "Default")
      (node (ref "IC2") (pin "5") (pinfunction "RT/CLK_5") (pintype "input"))
      (node (ref "R8") (pin "2") (pinfunction "2_2") (pintype "passive"))
    )
    (net (code "72") (name "Net-(IC2-SS{slash}TR)") (class "Default")
      (node (ref "C15") (pin "1") (pinfunction "1_1") (pintype "passive"))
      (node (ref "IC2") (pin "4") (pinfunction "SS/TR_4") (pintype "input"))
    )
    (net (code "73") (name "Net-(IC2-VSENSE)") (class "Default")
      (node (ref "IC2") (pin "7") (pinfunction "VSENSE_7") (pintype "input"))
      (node (ref "R10") (pin "2") (pinfunction "2_2") (pintype "passive"))
      (node (ref "R7") (pin "1") (pinfunction "1_1") (pintype "passive"))
    )
    (net (code "74") (name "Net-(IC3-B1)") (class "Default")
      (node (ref "IC3") (pin "14") (pinfunction "B1_14") (pintype "output"))
      (node (ref "RN1") (pin "4") (pinfunction "1_4") (pintype "passive"))
    )
    (net (code "75") (name "Net-(IC5-BYPASS)") (class "Default")
      (node (ref "C23") (pin "2") (pinfunction "2_2") (pintype "passive"))
      (node (ref "IC5") (pin "4") (pinfunction "BYPASS_4") (pintype "passive"))
    )
    (net (code "76") (name "Net-(IC6A-O)") (class "Default")
      (node (ref "IC6") (pin "6") (pinfunction "O_6") (pintype "output"))
      (node (ref "R16") (pin "2") (pinfunction "2_2") (pintype "passive"))
    )
    (net (code "77") (name "Net-(IC6B-O)") (class "Default")
      (node (ref "IC6") (pin "4") (pinfunction "O_4") (pintype "output"))
      (node (ref "R18") (pin "2") (pinfunction "2_2") (pintype "passive"))
    )
    (net (code "78") (name "Net-(IC7-IO1)") (class "Default")
      (node (ref "IC7") (pin "1") (pinfunction "IO1_1") (pintype "bidirectional"))
      (node (ref "RN2") (pin "8") (pinfunction "2_8") (pintype "passive"))
      (node (ref "X3") (pin "6") (pinfunction "S_6") (pintype "passive"))
    )
    (net (code "79") (name "Net-(IC7-IO2)") (class "Default")
      (node (ref "IC7") (pin "2") (pinfunction "IO2_2") (pintype "bidirectional"))
      (node (ref "RN2") (pin "6") (pinfunction "2_6") (pintype "passive"))
      (node (ref "X3") (pin "5") (pinfunction "S_5") (pintype "passive"))
    )
    (net (code "80") (name "Net-(IC8-PB5)") (class "Default")
      (node (ref "IC8") (pin "41") (pinfunction "PB5_41") (pintype "bidirectional"))
      (node (ref "OE#1") (pin "1") (pinfunction "1_1") (pintype "passive"))
    )
    (net (code "81") (name "Net-(IC8-PB6)") (class "Default")
      (node (ref "IC8") (pin "42") (pinfunction "PB6_42") (pintype "bidirectional"))
      (node (ref "OE#2") (pin "1") (pinfunction "1_1") (pintype "passive"))
    )
    (net (code "82") (name "Net-(IC8-PF0-OSC_IN)") (class "Default")
      (node (ref "C32") (pin "2") (pinfunction "2_2") (pintype "passive"))
      (node (ref "IC8") (pin "5") (pinfunction "PF0-OSC_IN_5") (pintype "bidirectional"))
      (node (ref "Y1") (pin "3") (pinfunction "2_3") (pintype "passive"))
    )
    (net (code "83") (name "Net-(IC8-PF1-OSC_OUT)") (class "Default")
      (node (ref "C33") (pin "2") (pinfunction "2_2") (pintype "passive"))
      (node (ref "IC8") (pin "6") (pinfunction "PF1-OSC_OUT_6") (pintype "bidirectional"))
      (node (ref "Y1") (pin "1") (pinfunction "1_1") (pintype "passive"))
    )
    (net (code "84") (name "Net-(IC10A-+IN)") (class "Default")
      (node (ref "IC10") (pin "3") (pinfunction "+IN_3") (pintype "input"))
      (node (ref "R56") (pin "2") (pinfunction "2_2") (pintype "passive"))
      (node (ref "R57") (pin "2") (pinfunction "2_2") (pintype "passive"))
    )
    (net (code "85") (name "Net-(IC10A--IN)") (class "Default")
      (node (ref "C69") (pin "2") (pinfunction "2_2") (pintype "passive"))
      (node (ref "IC10") (pin "2") (pinfunction "-IN_2") (pintype "input"))
      (node (ref "R54") (pin "2") (pinfunction "2_2") (pintype "passive"))
      (node (ref "R55") (pin "1") (pinfunction "1_1") (pintype "passive"))
    )
    (net (code "86") (name "Net-(IC10A-OUT)") (class "Default")
      (node (ref "C69") (pin "1") (pinfunction "1_1") (pintype "passive"))
      (node (ref "IC10") (pin "1") (pinfunction "OUT_1") (pintype "output"))
      (node (ref "IC13") (pin "14") (pinfunction "CTRL1_14") (pintype "input"))
      (node (ref "R55") (pin "2") (pinfunction "2_2") (pintype "passive"))
    )
    (net (code "87") (name "Net-(IC10B-+IN)") (class "Default")
      (node (ref "IC10") (pin "5") (pinfunction "+IN_5") (pintype "input"))
      (node (ref "R32") (pin "2") (pinfunction "2_2") (pintype "passive"))
      (node (ref "R33") (pin "2") (pinfunction "2_2") (pintype "passive"))
    )
    (net (code "88") (name "Net-(IC10B--IN)") (class "Default")
      (node (ref "C48") (pin "2") (pinfunction "2_2") (pintype "passive"))
      (node (ref "IC10") (pin "6") (pinfunction "-IN_6") (pintype "input"))
      (node (ref "R30") (pin "2") (pinfunction "2_2") (pintype "passive"))
      (node (ref "R31") (pin "1") (pinfunction "1_1") (pintype "passive"))
    )
    (net (code "89") (name "Net-(IC10B-OUT)") (class "Default")
      (node (ref "C48") (pin "1") (pinfunction "1_1") (pintype "passive"))
      (node (ref "IC10") (pin "7") (pinfunction "OUT_7") (pintype "output"))
      (node (ref "IC11") (pin "14") (pinfunction "CTRL1_14") (pintype "input"))
      (node (ref "R31") (pin "2") (pinfunction "2_2") (pintype "passive"))
    )
    (net (code "90") (name "Net-(IC11-BG)") (class "Default")
      (node (ref "IC11") (pin "1") (pinfunction "BG_1") (pintype "output"))
      (node (ref "Q3") (pin "1") (pinfunction "G_1") (pintype "passive"))
    )
    (net (code "91") (name "Net-(IC11-BOOST)") (class "Default")
      (node (ref "C54") (pin "1") (pinfunction "1_1") (pintype "passive"))
      (node (ref "D6") (pin "C") (pinfunction "C_C") (pintype "passive"))
      (node (ref "IC11") (pin "27") (pinfunction "BOOST_27") (pintype "passive"))
    )
    (net (code "92") (name "Net-(IC11-ISMON)") (class "Default")
      (node (ref "IC11") (pin "19") (pinfunction "ISMON_19") (pintype "output"))
      (node (ref "R38") (pin "2") (pinfunction "2_2") (pintype "passive"))
    )
    (net (code "93") (name "Net-(IC11-PWM)") (class "Default")
      (node (ref "IC11") (pin "22") (pinfunction "PWM_22") (pintype "input"))
      (node (ref "R43") (pin "2") (pinfunction "2_2") (pintype "passive"))
    )
    (net (code "94") (name "Net-(IC11-RT)") (class "Default")
      (node (ref "IC11") (pin "20") (pinfunction "RT_20") (pintype "input"))
      (node (ref "R42") (pin "2") (pinfunction "2_2") (pintype "passive"))
    )
    (net (code "95") (name "Net-(IC11-SENSE+)") (class "Default")
      (node (ref "C65") (pin "1") (pinfunction "1_1") (pintype "passive"))
      (node (ref "IC11") (pin "17") (pinfunction "SENSE+_17") (pintype "input"))
      (node (ref "R35") (pin "1") (pinfunction "1_1") (pintype "passive"))
    )
    (net (code "96") (name "Net-(IC11-SENSE-)") (class "Default")
      (node (ref "C65") (pin "2") (pinfunction "2_2") (pintype "passive"))
      (node (ref "IC11") (pin "16") (pinfunction "SENSE-_16") (pintype "input"))
      (node (ref "R36") (pin "1") (pinfunction "1_1") (pintype "passive"))
    )
    (net (code "97") (name "Net-(IC11-SS)") (class "Default")
      (node (ref "C66") (pin "2") (pinfunction "2_2") (pintype "passive"))
      (node (ref "IC11") (pin "15") (pinfunction "SS_15") (pintype "input"))
    )
    (net (code "98") (name "Net-(IC11-SW)") (class "Default")
      (node (ref "C54") (pin "2") (pinfunction "2_2") (pintype "passive"))
      (node (ref "C58") (pin "1") (pinfunction "1_1") (pintype "passive"))
      (node (ref "D7") (pin "C") (pinfunction "C_C") (pintype "passive"))
      (node (ref "IC11") (pin "26") (pinfunction "SW_26") (pintype "output"))
      (node (ref "L2") (pin "1") (pinfunction "1_1") (pintype "passive"))
      (node (ref "Q2") (pin "3") (pinfunction "S_3") (pintype "passive"))
      (node (ref "Q3") (pin "2") (pinfunction "D_2") (pintype "passive"))
    )
    (net (code "99") (name "Net-(IC11-TG)") (class "Default")
      (node (ref "IC11") (pin "25") (pinfunction "TG_25") (pintype "output"))
      (node (ref "Q2") (pin "1") (pinfunction "G_1") (pintype "passive"))
    )
    (net (code "100") (name "Net-(IC11-VC)") (class "Default")
      (node (ref "C67") (pin "2") (pinfunction "2_2") (pintype "passive"))
      (node (ref "IC11") (pin "18") (pinfunction "VC_18") (pintype "passive"))
    )
    (net (code "101") (name "Net-(IC11-VIN)") (class "Default")
      (node (ref "C49") (pin "1") (pinfunction "1_1") (pintype "passive"))
      (node (ref "D3") (pin "C") (pinfunction "C_C") (pintype "passive"))
      (node (ref "D5") (pin "C") (pinfunction "C_C") (pintype "passive"))
      (node (ref "IC11") (pin "3") (pinfunction "VIN_3") (pintype "passive"))
    )
    (net (code "102") (name "Net-(IC11-~{FAULT})") (class "Default")
      (node (ref "IC11") (pin "9") (pinfunction "~{FAULT}_9") (pintype "output"))
      (node (ref "R44") (pin "1") (pinfunction "1_1") (pintype "passive"))
    )
    (net (code "103") (name "Net-(IC12A-+IN)") (class "Default")
      (node (ref "IC12") (pin "3") (pinfunction "+IN_3") (pintype "input"))
      (node (ref "R74") (pin "1") (pinfunction "1_1") (pintype "passive"))
      (node (ref "R75") (pin "2") (pinfunction "2_2") (pintype "passive"))
    )
    (net (code "104") (name "Net-(IC12A--IN)") (class "Default")
      (node (ref "IC12") (pin "13") (pinfunction "-IN_13") (pintype "input"))
      (node (ref "IC12") (pin "14") (pinfunction "OUT_14") (pintype "output"))
      (node (ref "IC12") (pin "2") (pinfunction "-IN_2") (pintype "input"))
    )
    (net (code "105") (name "Net-(IC12B-+IN)") (class "Default")
      (node (ref "IC12") (pin "5") (pinfunction "+IN_5") (pintype "input"))
      (node (ref "R50") (pin "1") (pinfunction "1_1") (pintype "passive"))
      (node (ref "R51") (pin "2") (pinfunction "2_2") (pintype "passive"))
    )
    (net (code "106") (name "Net-(IC12B--IN)") (class "Default")
      (node (ref "IC12") (pin "6") (pinfunction "-IN_6") (pintype "input"))
      (node (ref "IC12") (pin "8") (pinfunction "OUT_8") (pintype "output"))
      (node (ref "IC12") (pin "9") (pinfunction "-IN_9") (pintype "input"))
    )
    (net (code "107") (name "Net-(IC13-BG)") (class "Default")
      (node (ref "IC13") (pin "1") (pinfunction "BG_1") (pintype "output"))
      (node (ref "Q8") (pin "1") (pinfunction "G_1") (pintype "passive"))
    )
    (net (code "108") (name "Net-(IC13-BOOST)") (class "Default")
      (node (ref "C74") (pin "1") (pinfunction "1_1") (pintype "passive"))
      (node (ref "D11") (pin "C") (pinfunction "C_C") (pintype "passive"))
      (node (ref "IC13") (pin "27") (pinfunction "BOOST_27") (pintype "passive"))
    )
    (net (code "109") (name "Net-(IC13-ISMON)") (class "Default")
      (node (ref "IC13") (pin "19") (pinfunction "ISMON_19") (pintype "output"))
      (node (ref "R62") (pin "2") (pinfunction "2_2") (pintype "passive"))
    )
    (net (code "110") (name "Net-(IC13-PWM)") (class "Default")
      (node (ref "IC13") (pin "22") (pinfunction "PWM_22") (pintype "input"))
      (node (ref "R67") (pin "2") (pinfunction "2_2") (pintype "passive"))
    )
    (net (code "111") (name "Net-(IC13-RT)") (class "Default")
      (node (ref "IC13") (pin "20") (pinfunction "RT_20") (pintype "input"))
      (node (ref "R66") (pin "2") (pinfunction "2_2") (pintype "passive"))
    )
    (net (code "112") (name "Net-(IC13-SENSE+)") (class "Default")
      (node (ref "C85") (pin "1") (pinfunction "1_1") (pintype "passive"))
      (node (ref "IC13") (pin "17") (pinfunction "SENSE+_17") (pintype "input"))
      (node (ref "R59") (pin "1") (pinfunction "1_1") (pintype "passive"))
    )
    (net (code "113") (name "Net-(IC13-SENSE-)") (class "Default")
      (node (ref "C85") (pin "2") (pinfunction "2_2") (pintype "passive"))
      (node (ref "IC13") (pin "16") (pinfunction "SENSE-_16") (pintype "input"))
      (node (ref "R60") (pin "1") (pinfunction "1_1") (pintype "passive"))
    )
    (net (code "114") (name "Net-(IC13-SS)") (class "Default")
      (node (ref "C86") (pin "2") (pinfunction "2_2") (pintype "passive"))
      (node (ref "IC13") (pin "15") (pinfunction "SS_15") (pintype "input"))
    )
    (net (code "115") (name "Net-(IC13-SW)") (class "Default")
      (node (ref "C74") (pin "2") (pinfunction "2_2") (pintype "passive"))
      (node (ref "C78") (pin "1") (pinfunction "1_1") (pintype "passive"))
      (node (ref "D12") (pin "C") (pinfunction "C_C") (pintype "passive"))
      (node (ref "IC13") (pin "26") (pinfunction "SW_26") (pintype "output"))
      (node (ref "L4") (pin "1") (pinfunction "1_1") (pintype "passive"))
      (node (ref "Q7") (pin "3") (pinfunction "S_3") (pintype "passive"))
      (node (ref "Q8") (pin "2") (pinfunction "D_2") (pintype "passive"))
    )
    (net (code "116") (name "Net-(IC13-TG)") (class "Default")
      (node (ref "IC13") (pin "25") (pinfunction "TG_25") (pintype "output"))
      (node (ref "Q7") (pin "1") (pinfunction "G_1") (pintype "passive"))
    )
    (net (code "117") (name "Net-(IC13-VC)") (class "Default")
      (node (ref "C87") (pin "2") (pinfunction "2_2") (pintype "passive"))
      (node (ref "IC13") (pin "18") (pinfunction "VC_18") (pintype "passive"))
    )
    (net (code "118") (name "Net-(IC13-VIN)") (class "Default")
      (node (ref "C70") (pin "1") (pinfunction "1_1") (pintype "passive"))
      (node (ref "D10") (pin "C") (pinfunction "C_C") (pintype "passive"))
      (node (ref "D8") (pin "C") (pinfunction "C_C") (pintype "passive"))
      (node (ref "IC13") (pin "3") (pinfunction "VIN_3") (pintype "passive"))
    )
    (net (code "119") (name "Net-(IC13-~{FAULT})") (class "Default")
      (node (ref "IC13") (pin "9") (pinfunction "~{FAULT}_9") (pintype "output"))
      (node (ref "R68") (pin "1") (pinfunction "1_1") (pintype "passive"))
    )
    (net (code "120") (name "Net-(L1A-1)") (class "Default")
      (node (ref "C1") (pin "2") (pinfunction "2_2") (pintype "passive"))
      (node (ref "L1") (pin "3") (pinfunction "1_3") (pintype "passive"))
      (node (ref "R1") (pin "2") (pinfunction "2_2") (pintype "passive"))
      (node (ref "X1") (pin "1") (pinfunction "1_1") (pintype "passive"))
    )
    (net (code "121") (name "Net-(L2-Pad2)") (class "Default")
      (node (ref "L2") (pin "2") (pinfunction "2_2") (pintype "passive"))
      (node (ref "R34") (pin "1") (pinfunction "1_1") (pintype "passive"))
    )
    (net (code "122") (name "Net-(L4-Pad2)") (class "Default")
      (node (ref "L4") (pin "2") (pinfunction "2_2") (pintype "passive"))
      (node (ref "R58") (pin "1") (pinfunction "1_1") (pintype "passive"))
    )
    (net (code "123") (name "Net-(LED1-AG)") (class "Default")
      (node (ref "LED1") (pin "GREEN") (pinfunction "AG_GREEN") (pintype "passive"))
      (node (ref "Q4") (pin "2") (pinfunction "S_2") (pintype "passive"))
    )
    (net (code "124") (name "Net-(LED1-AR)") (class "Default")
      (node (ref "LED1") (pin "RED") (pinfunction "AR_RED") (pintype "passive"))
      (node (ref "R49") (pin "1") (pinfunction "1_1") (pintype "passive"))
    )
    (net (code "125") (name "Net-(LED2-AG)") (class "Default")
      (node (ref "LED2") (pin "GREEN") (pinfunction "AG_GREEN") (pintype "passive"))
      (node (ref "Q9") (pin "2") (pinfunction "S_2") (pintype "passive"))
    )
    (net (code "126") (name "Net-(LED2-AR)") (class "Default")
      (node (ref "LED2") (pin "RED") (pinfunction "AR_RED") (pintype "passive"))
      (node (ref "R73") (pin "1") (pinfunction "1_1") (pintype "passive"))
    )
    (net (code "127") (name "Net-(Q1-D-Pad2)") (class "Default")
      (node (ref "Q1") (pin "2") (pinfunction "D_2") (pintype "passive"))
      (node (ref "Q1") (pin "4") (pinfunction "D_4") (pintype "passive"))
      (node (ref "R28") (pin "2") (pinfunction "2_2") (pintype "passive"))
    )
    (net (code "128") (name "Net-(Q1-G)") (class "Default")
      (node (ref "D4") (pin "C") (pinfunction "C_C") (pintype "passive"))
      (node (ref "Q1") (pin "1") (pinfunction "G_1") (pintype "passive"))
      (node (ref "R29") (pin "2") (pinfunction "2_2") (pintype "passive"))
      (node (ref "ZD2") (pin "C") (pinfunction "C_C") (pintype "passive"))
    )
    (net (code "129") (name "Net-(Q1-S)") (class "Default")
      (node (ref "D3") (pin "A") (pinfunction "A_A") (pintype "passive"))
      (node (ref "D4") (pin "A") (pinfunction "A_A") (pintype "passive"))
      (node (ref "Q1") (pin "3") (pinfunction "S_3") (pintype "passive"))
    )
    (net (code "130") (name "Net-(Q4-D)") (class "Default")
      (node (ref "Q4") (pin "3") (pinfunction "D_3") (pintype "passive"))
      (node (ref "Q5") (pin "3") (pinfunction "D_3") (pintype "passive"))
    )
    (net (code "131") (name "Net-(Q6-D-Pad2)") (class "Default")
      (node (ref "Q6") (pin "2") (pinfunction "D_2") (pintype "passive"))
      (node (ref "Q6") (pin "4") (pinfunction "D_4") (pintype "passive"))
      (node (ref "R52") (pin "2") (pinfunction "2_2") (pintype "passive"))
    )
    (net (code "132") (name "Net-(Q6-G)") (class "Default")
      (node (ref "D9") (pin "C") (pinfunction "C_C") (pintype "passive"))
      (node (ref "Q6") (pin "1") (pinfunction "G_1") (pintype "passive"))
      (node (ref "R53") (pin "2") (pinfunction "2_2") (pintype "passive"))
      (node (ref "ZD4") (pin "C") (pinfunction "C_C") (pintype "passive"))
    )
    (net (code "133") (name "Net-(Q6-S)") (class "Default")
      (node (ref "D8") (pin "A") (pinfunction "A_A") (pintype "passive"))
      (node (ref "D9") (pin "A") (pinfunction "A_A") (pintype "passive"))
      (node (ref "Q6") (pin "3") (pinfunction "S_3") (pintype "passive"))
    )
    (net (code "134") (name "Net-(Q10-D)") (class "Default")
      (node (ref "Q10") (pin "3") (pinfunction "D_3") (pintype "passive"))
      (node (ref "Q9") (pin "3") (pinfunction "D_3") (pintype "passive"))
    )
    (net (code "135") (name "Net-(R34-Pad1S)") (class "Default")
      (node (ref "R34") (pin "1S") (pinfunction "1S_1S") (pintype "passive"))
      (node (ref "R35") (pin "2") (pinfunction "2_2") (pintype "passive"))
    )
    (net (code "136") (name "Net-(R34-Pad2S)") (class "Default")
      (node (ref "R34") (pin "2S") (pinfunction "2S_2S") (pintype "passive"))
      (node (ref "R36") (pin "2") (pinfunction "2_2") (pintype "passive"))
    )
    (net (code "137") (name "Net-(R58-Pad1S)") (class "Default")
      (node (ref "R58") (pin "1S") (pinfunction "1S_1S") (pintype "passive"))
      (node (ref "R59") (pin "2") (pinfunction "2_2") (pintype "passive"))
    )
    (net (code "138") (name "Net-(R58-Pad2S)") (class "Default")
      (node (ref "R58") (pin "2S") (pinfunction "2S_2S") (pintype "passive"))
      (node (ref "R60") (pin "2") (pinfunction "2_2") (pintype "passive"))
    )
    (net (code "139") (name "Net-(X1B-1)") (class "Default")
      (node (ref "C1") (pin "1") (pinfunction "1_1") (pintype "passive"))
      (node (ref "L1") (pin "1") (pinfunction "1_1") (pintype "passive"))
      (node (ref "R1") (pin "1") (pinfunction "1_1") (pintype "passive"))
      (node (ref "X1") (pin "2") (pinfunction "1_2") (pintype "passive"))
    )
    (net (code "140") (name "Net-(X3A-S)") (class "Default")
      (node (ref "JP2") (pin "2") (pinfunction "2_2") (pintype "passive"))
      (node (ref "R19") (pin "2") (pinfunction "2_2") (pintype "passive"))
      (node (ref "X3") (pin "1") (pinfunction "S_1") (pintype "passive"))
    )
    (net (code "141") (name "OE#1") (class "Default")
      (node (ref "IC11") (pin "4") (pinfunction "EV/UVLO_4") (pintype "input"))
      (node (ref "OE#1") (pin "2") (pinfunction "2_2") (pintype "passive"))
      (node (ref "Q4") (pin "1") (pinfunction "G_1") (pintype "passive"))
    )
    (net (code "142") (name "OE#2") (class "Default")
      (node (ref "IC13") (pin "4") (pinfunction "EV/UVLO_4") (pintype "input"))
      (node (ref "OE#2") (pin "2") (pinfunction "2_2") (pintype "passive"))
      (node (ref "Q9") (pin "1") (pinfunction "G_1") (pintype "passive"))
    )
    (net (code "143") (name "OE_SYNC") (class "Default")
      (node (ref "IC8") (pin "36") (pinfunction "PF7_36") (pintype "bidirectional"))
      (node (ref "RN1") (pin "8") (pinfunction "2_8") (pintype "passive"))
    )
    (net (code "144") (name "PE") (class "Default")
      (node (ref "C2") (pin "2") (pinfunction "2_2") (pintype "passive"))
      (node (ref "C3") (pin "1") (pinfunction "1_1") (pintype "passive"))
      (node (ref "C56") (pin "1") (pinfunction "1_1") (pintype "passive"))
      (node (ref "C63") (pin "1") (pinfunction "1_1") (pintype "passive"))
      (node (ref "C76") (pin "1") (pinfunction "1_1") (pintype "passive"))
      (node (ref "C83") (pin "1") (pinfunction "1_1") (pintype "passive"))
      (node (ref "J1") (pin "1") (pinfunction "P$1_1") (pintype "bidirectional"))
      (node (ref "J1") (pin "2") (pinfunction "P$1_2") (pintype "bidirectional"))
    )
    (net (code "145") (name "PWRGOOD") (class "Default")
      (node (ref "IC2") (pin "6") (pinfunction "PWRGD_6") (pintype "output"))
      (node (ref "IC8") (pin "40") (pinfunction "PB4_40") (pintype "bidirectional"))
    )
    (net (code "146") (name "SCLK") (class "Default")
      (node (ref "IC8") (pin "29") (pinfunction "PA8_29") (pintype "bidirectional"))
      (node (ref "RN1") (pin "7") (pinfunction "2_7") (pintype "passive"))
    )
    (net (code "147") (name "SWCLK") (class "Default")
      (node (ref "IC8") (pin "37") (pinfunction "PA14_37") (pintype "bidirectional"))
      (node (ref "RN2") (pin "2") (pinfunction "1_2") (pintype "passive"))
    )
    (net (code "148") (name "SWDIO") (class "Default")
      (node (ref "IC8") (pin "34") (pinfunction "PA13_34") (pintype "bidirectional"))
      (node (ref "RN2") (pin "4") (pinfunction "1_4") (pintype "passive"))
    )
    (net (code "149") (name "SWO") (class "Default")
      (node (ref "IC8") (pin "39") (pinfunction "PB3_39") (pintype "bidirectional"))
      (node (ref "RN2") (pin "1") (pinfunction "1_1") (pintype "passive"))
    )
    (net (code "150") (name "TCK") (class "Default")
      (node (ref "IC7") (pin "5") (pinfunction "IO4_5") (pintype "bidirectional"))
      (node (ref "RN2") (pin "7") (pinfunction "2_7") (pintype "passive"))
      (node (ref "X3") (pin "2") (pinfunction "S_2") (pintype "passive"))
    )
    (net (code "151") (name "TEMP#1") (class "Default")
      (node (ref "C34") (pin "2") (pinfunction "2_2") (pintype "passive"))
      (node (ref "IC8") (pin "10") (pinfunction "PA0_10") (pintype "bidirectional"))
      (node (ref "NTC1") (pin "2") (pinfunction "P$2_2") (pintype "bidirectional"))
      (node (ref "R21") (pin "1") (pinfunction "1_1") (pintype "passive"))
    )
    (net (code "152") (name "TEMP#2") (class "Default")
      (node (ref "C35") (pin "2") (pinfunction "2_2") (pintype "passive"))
      (node (ref "IC8") (pin "14") (pinfunction "PA4_14") (pintype "bidirectional"))
      (node (ref "NTC2") (pin "2") (pinfunction "P$2_2") (pintype "bidirectional"))
      (node (ref "R22") (pin "1") (pinfunction "1_1") (pintype "passive"))
    )
    (net (code "153") (name "TMS") (class "Default")
      (node (ref "IC7") (pin "4") (pinfunction "IO3_4") (pintype "bidirectional"))
      (node (ref "RN2") (pin "5") (pinfunction "2_5") (pintype "passive"))
      (node (ref "X3") (pin "4") (pinfunction "S_4") (pintype "passive"))
    )
    (net (code "154") (name "UART_RX") (class "Default")
      (node (ref "IC3") (pin "12") (pinfunction "B3_12") (pintype "output"))
      (node (ref "IC8") (pin "13") (pinfunction "PA3_13") (pintype "bidirectional"))
    )
    (net (code "155") (name "UART_TX") (class "Default")
      (node (ref "IC3") (pin "11") (pinfunction "B4_11") (pintype "input"))
      (node (ref "IC8") (pin "12") (pinfunction "PA2_12") (pintype "bidirectional"))
    )
    (net (code "156") (name "U_MON#1") (class "Default")
      (node (ref "C41") (pin "2") (pinfunction "2_2") (pintype "passive"))
      (node (ref "IC8") (pin "18") (pinfunction "PB0_18") (pintype "bidirectional"))
      (node (ref "R24") (pin "1") (pinfunction "1_1") (pintype "passive"))
    )
    (net (code "157") (name "U_MON#2") (class "Default")
      (node (ref "C43") (pin "2") (pinfunction "2_2") (pintype "passive"))
      (node (ref "IC8") (pin "20") (pinfunction "PB2_20") (pintype "bidirectional"))
      (node (ref "R26") (pin "1") (pinfunction "1_1") (pintype "passive"))
    )
    (net (code "158") (name "U_MON1") (class "Default")
      (node (ref "R24") (pin "2") (pinfunction "2_2") (pintype "passive"))
      (node (ref "R40") (pin "1") (pinfunction "1_1") (pintype "passive"))
      (node (ref "R47") (pin "2") (pinfunction "2_2") (pintype "passive"))
    )
    (net (code "159") (name "U_MON2") (class "Default")
      (node (ref "R26") (pin "2") (pinfunction "2_2") (pintype "passive"))
      (node (ref "R64") (pin "1") (pinfunction "1_1") (pintype "passive"))
      (node (ref "R71") (pin "2") (pinfunction "2_2") (pintype "passive"))
    )
    (net (code "160") (name "U_SET#1") (class "Default")
      (node (ref "R48") (pin "1") (pinfunction "1_1") (pintype "passive"))
      (node (ref "U_SET1") (pin "1") (pinfunction "1_1") (pintype "passive"))
    )
    (net (code "161") (name "U_SET#2") (class "Default")
      (node (ref "R72") (pin "1") (pinfunction "1_1") (pintype "passive"))
      (node (ref "U_SET2") (pin "1") (pinfunction "1_1") (pintype "passive"))
    )
    (net (code "162") (name "U_SET_OUT#1") (class "Default")
      (node (ref "IC8") (pin "16") (pinfunction "PA6_16") (pintype "bidirectional"))
      (node (ref "U_SET1") (pin "2") (pinfunction "2_2") (pintype "passive"))
    )
    (net (code "163") (name "U_SET_OUT#2") (class "Default")
      (node (ref "IC8") (pin "15") (pinfunction "PA5_15") (pintype "bidirectional"))
      (node (ref "U_SET2") (pin "2") (pinfunction "2_2") (pintype "passive"))
    )
    (net (code "164") (name "V+") (class "Default")
      (node (ref "C17") (pin "1") (pinfunction "1_1") (pintype "passive"))
      (node (ref "C20") (pin "2") (pinfunction "2_2") (pintype "passive"))
      (node (ref "C7") (pin "1") (pinfunction "1_1") (pintype "passive"))
      (node (ref "IC1") (pin "1") (pinfunction "VDD1_1") (pintype "passive"))
      (node (ref "IC3") (pin "1") (pinfunction "VDD1_1") (pintype "passive"))
      (node (ref "IC3") (pin "7") (pinfunction "EN1_7") (pintype "input"))
      (node (ref "IC4") (pin "8") (pinfunction "VCC_8") (pintype "power_in"))
      (node (ref "R11") (pin "1") (pinfunction "1_1") (pintype "passive"))
      (node (ref "R12") (pin "1") (pinfunction "1_1") (pintype "passive"))
      (node (ref "R13") (pin "1") (pinfunction "1_1") (pintype "passive"))
      (node (ref "X2") (pin "1") (pinfunction "1_1") (pintype "passive"))
    )
    (net (code "165") (name "VDDA") (class "Default")
      (node (ref "C37") (pin "2") (pinfunction "2_2") (pintype "passive"))
      (node (ref "C38") (pin "2") (pinfunction "2_2") (pintype "passive"))
      (node (ref "FB1") (pin "P$2") (pinfunction "2_P$2") (pintype "passive"))
      (node (ref "IC8") (pin "24") (pinfunction "VDDSD_24") (pintype "passive"))
    )
    (net (code "166") (name "VOUT1+") (class "Default")
      (node (ref "C59") (pin "1") (pinfunction "1_1") (pintype "passive"))
      (node (ref "C60") (pin "1") (pinfunction "1_1") (pintype "passive"))
      (node (ref "C62") (pin "+") (pinfunction "+_+") (pintype "passive"))
      (node (ref "L3") (pin "1") (pinfunction "1_1") (pintype "passive"))
      (node (ref "R34") (pin "2") (pinfunction "2_2") (pintype "passive"))
      (node (ref "R39") (pin "2") (pinfunction "2_2") (pintype "passive"))
      (node (ref "R40") (pin "2") (pinfunction "2_2") (pintype "passive"))
      (node (ref "ZD2") (pin "A") (pinfunction "A_A") (pintype "passive"))
    )
    (net (code "167") (name "VOUT2+") (class "Default")
      (node (ref "C79") (pin "1") (pinfunction "1_1") (pintype "passive"))
      (node (ref "C80") (pin "1") (pinfunction "1_1") (pintype "passive"))
      (node (ref "C82") (pin "+") (pinfunction "+_+") (pintype "passive"))
      (node (ref "L5") (pin "1") (pinfunction "1_1") (pintype "passive"))
      (node (ref "R58") (pin "2") (pinfunction "2_2") (pintype "passive"))
      (node (ref "R63") (pin "2") (pinfunction "2_2") (pintype "passive"))
      (node (ref "R64") (pin "2") (pinfunction "2_2") (pintype "passive"))
      (node (ref "ZD4") (pin "A") (pinfunction "A_A") (pintype "passive"))
    )
    (net (code "168") (name "VOUT_LC1+") (class "Default")
      (node (ref "C56") (pin "2") (pinfunction "2_2") (pintype "passive"))
      (node (ref "C57") (pin "1") (pinfunction "1_1") (pintype "passive"))
      (node (ref "C61") (pin "1") (pinfunction "+_1") (pintype "passive"))
      (node (ref "CH1") (pin "TIP") (pinfunction "TIP_TIP") (pintype "bidirectional"))
      (node (ref "J2") (pin "1") (pinfunction "1_1") (pintype "passive"))
      (node (ref "J2") (pin "1.1") (pinfunction "1_1.1") (pintype "passive"))
      (node (ref "L3") (pin "2") (pinfunction "2_2") (pintype "passive"))
      (node (ref "R41") (pin "1") (pinfunction "1_1") (pintype "passive"))
      (node (ref "ZD3") (pin "C") (pinfunction "C_C") (pintype "passive"))
    )
    (net (code "169") (name "VOUT_LC2+") (class "Default")
      (node (ref "C76") (pin "2") (pinfunction "2_2") (pintype "passive"))
      (node (ref "C77") (pin "1") (pinfunction "1_1") (pintype "passive"))
      (node (ref "C81") (pin "1") (pinfunction "+_1") (pintype "passive"))
      (node (ref "CH2") (pin "TIP") (pinfunction "TIP_TIP") (pintype "bidirectional"))
      (node (ref "J4") (pin "1") (pinfunction "1_1") (pintype "passive"))
      (node (ref "J4") (pin "1.1") (pinfunction "1_1.1") (pintype "passive"))
      (node (ref "L5") (pin "2") (pinfunction "2_2") (pintype "passive"))
      (node (ref "R65") (pin "1") (pinfunction "1_1") (pintype "passive"))
      (node (ref "ZD5") (pin "C") (pinfunction "C_C") (pintype "passive"))
    )
    (net (code "170") (name "VREF1") (class "Default")
      (node (ref "C53") (pin "1") (pinfunction "1_1") (pintype "passive"))
      (node (ref "IC11") (pin "10") (pinfunction "FBIN_10") (pintype "input"))
      (node (ref "IC11") (pin "13") (pinfunction "CTRL2_13") (pintype "input"))
      (node (ref "IC11") (pin "5") (pinfunction "VREF_5") (pintype "output"))
      (node (ref "R50") (pin "2") (pinfunction "2_2") (pintype "passive"))
    )
    (net (code "171") (name "VREF2") (class "Default")
      (node (ref "C73") (pin "1") (pinfunction "1_1") (pintype "passive"))
      (node (ref "IC13") (pin "10") (pinfunction "FBIN_10") (pintype "input"))
      (node (ref "IC13") (pin "13") (pinfunction "CTRL2_13") (pintype "input"))
      (node (ref "IC13") (pin "5") (pinfunction "VREF_5") (pintype "output"))
      (node (ref "R74") (pin "2") (pinfunction "2_2") (pintype "passive"))
    )
    (net (code "172") (name "unconnected-(IC8-PA15-Pad38)") (class "Default")
      (node (ref "IC8") (pin "38") (pinfunction "PA15_38") (pintype "bidirectional"))
    )
    (net (code "173") (name "unconnected-(IC8-PB7-Pad43)") (class "Default")
      (node (ref "IC8") (pin "43") (pinfunction "PB7_43") (pintype "bidirectional"))
    )
    (net (code "174") (name "unconnected-(IC8-PB14-Pad26)") (class "Default")
      (node (ref "IC8") (pin "26") (pinfunction "PB14_26") (pintype "bidirectional"))
    )
    (net (code "175") (name "unconnected-(IC8-PB15-Pad27)") (class "Default")
      (node (ref "IC8") (pin "27") (pinfunction "PB15_27") (pintype "bidirectional"))
    )
    (net (code "176") (name "unconnected-(IC8-PD8-Pad28)") (class "Default")
      (node (ref "IC8") (pin "28") (pinfunction "PD8_28") (pintype "bidirectional"))
    )
    (net (code "177") (name "unconnected-(IC8-PE9-Pad22)") (class "Default")
      (node (ref "IC8") (pin "22") (pinfunction "PE9_22") (pintype "bidirectional"))
    )
    (net (code "178") (name "unconnected-(IC8-PF6-Pad35)") (class "Default")
      (node (ref "IC8") (pin "35") (pinfunction "PF6_35") (pintype "bidirectional"))
    )
    (net (code "179") (name "unconnected-(IC8-VBAT-Pad1)") (class "Default")
      (node (ref "IC8") (pin "1") (pinfunction "VBAT_1") (pintype "passive"))
    )
    (net (code "180") (name "unconnected-(IC11-IVINMON-Pad8)") (class "Default")
      (node (ref "IC11") (pin "8") (pinfunction "IVINMON_8") (pintype "output"))
    )
    (net (code "181") (name "unconnected-(IC11-PWMOUT-Pad24)") (class "Default")
      (node (ref "IC11") (pin "24") (pinfunction "PWMOUT_24") (pintype "output"))
    )
    (net (code "182") (name "unconnected-(IC13-IVINMON-Pad8)") (class "Default")
      (node (ref "IC13") (pin "8") (pinfunction "IVINMON_8") (pintype "output"))
    )
    (net (code "183") (name "unconnected-(IC13-PWMOUT-Pad24)") (class "Default")
      (node (ref "IC13") (pin "24") (pinfunction "PWMOUT_24") (pintype "output"))
    )
    (net (code "184") (name "~{RESET}") (class "Default")
      (node (ref "IC1") (pin "15") (pinfunction "B1_15") (pintype "output"))
      (node (ref "JP3") (pin "1") (pinfunction "1_1") (pintype "passive"))
    )
  )
)
